# PM_Controller_v1p04.net
KiCad netlist of a schematic drawn in EAGLE
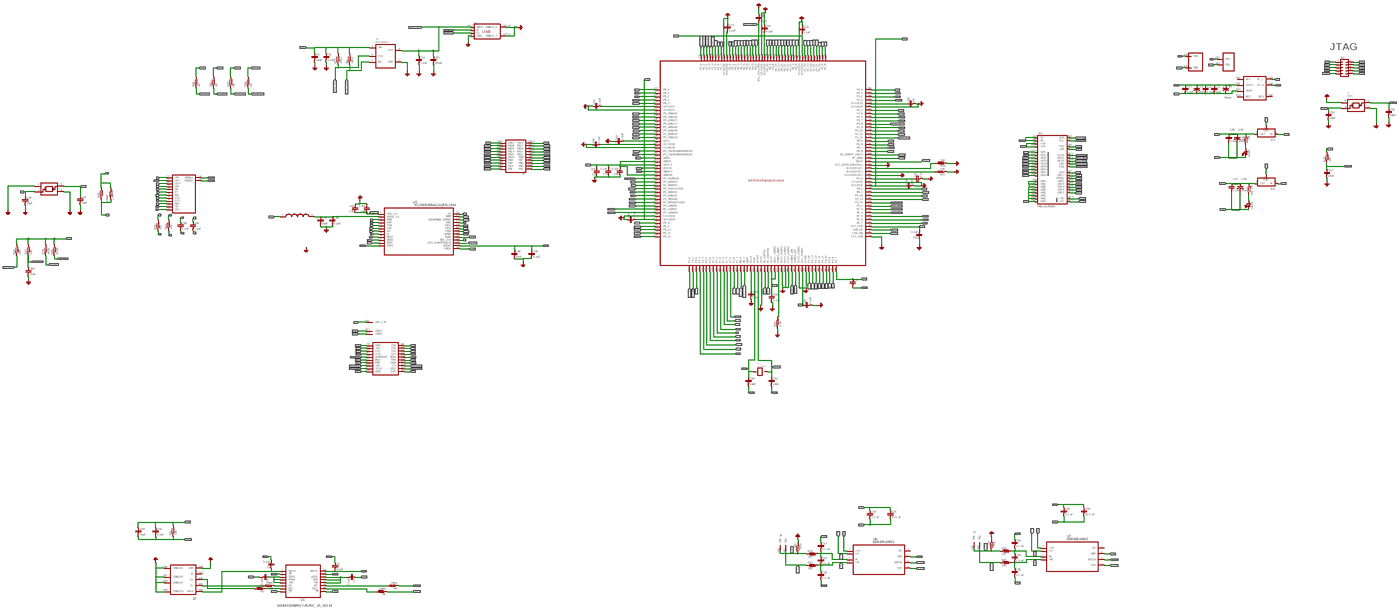
[diagram p0: schematic, sheet 1, overview]
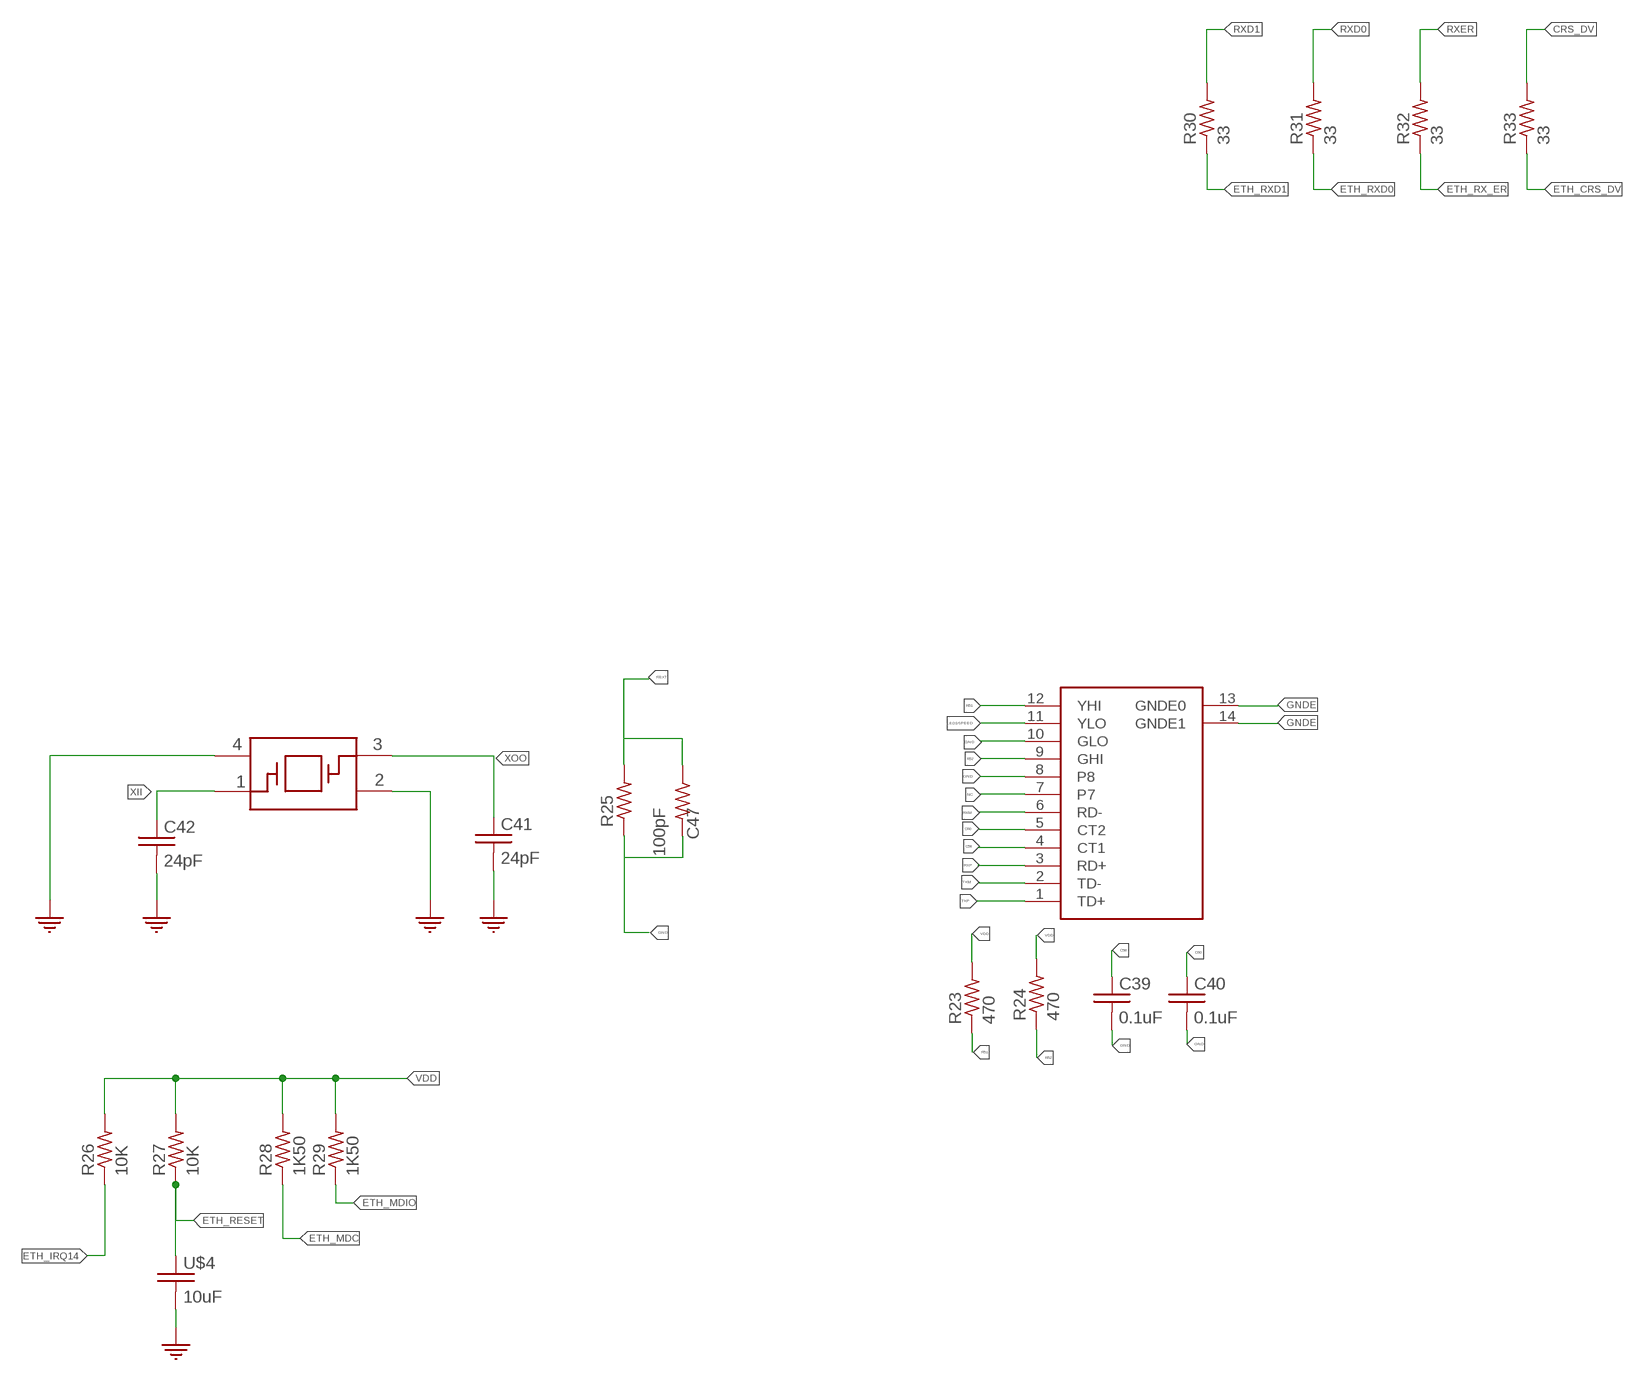
[diagram p1: schematic, sheet 1, part 1 of 7]
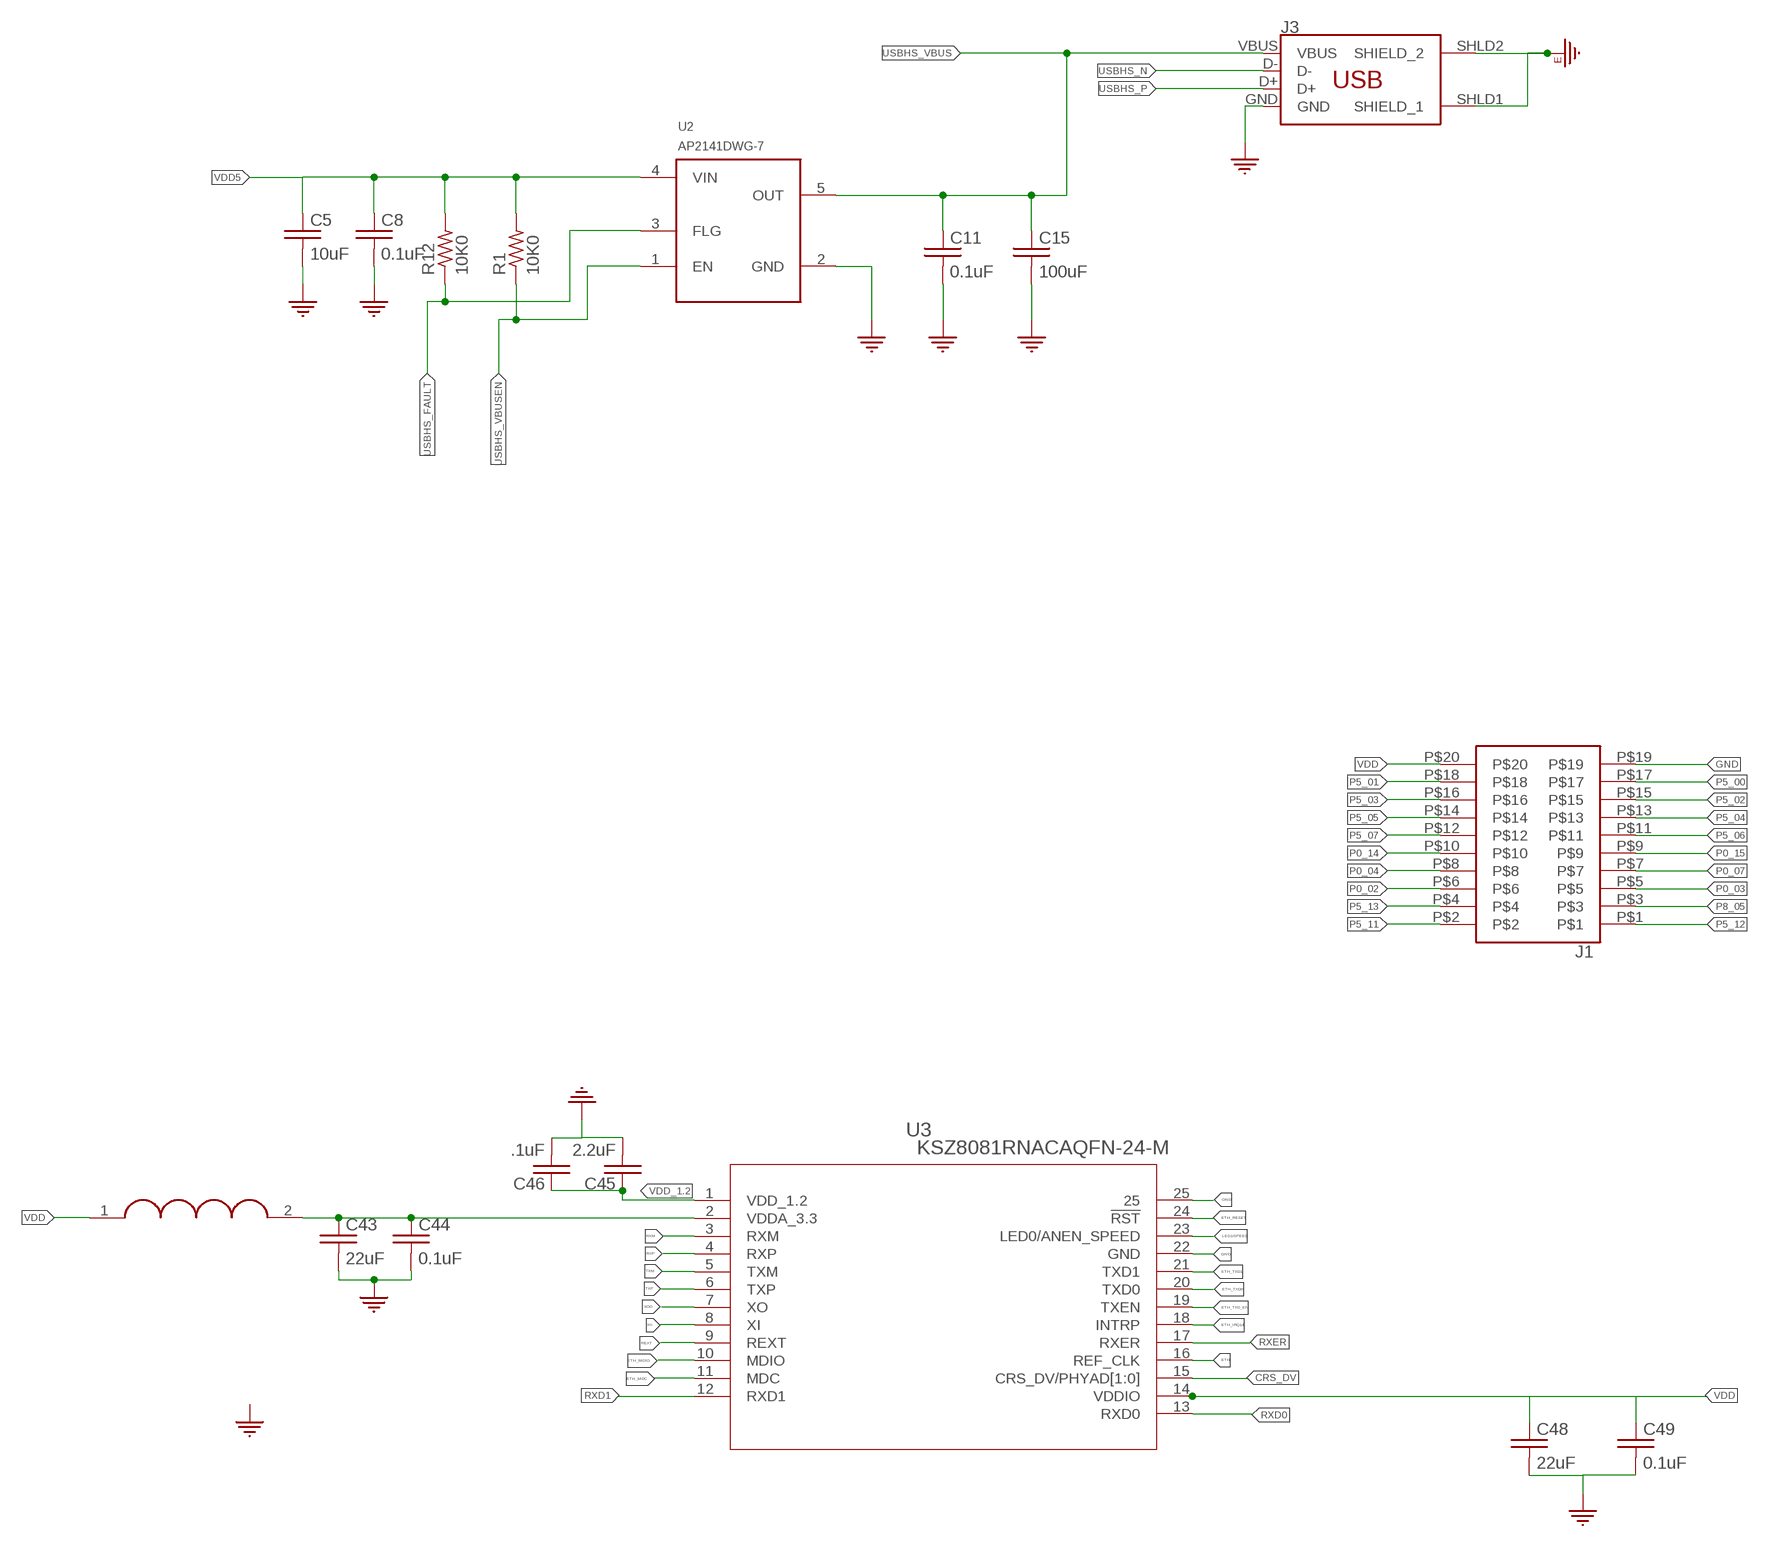
[diagram p2: schematic, sheet 1, part 2 of 7]
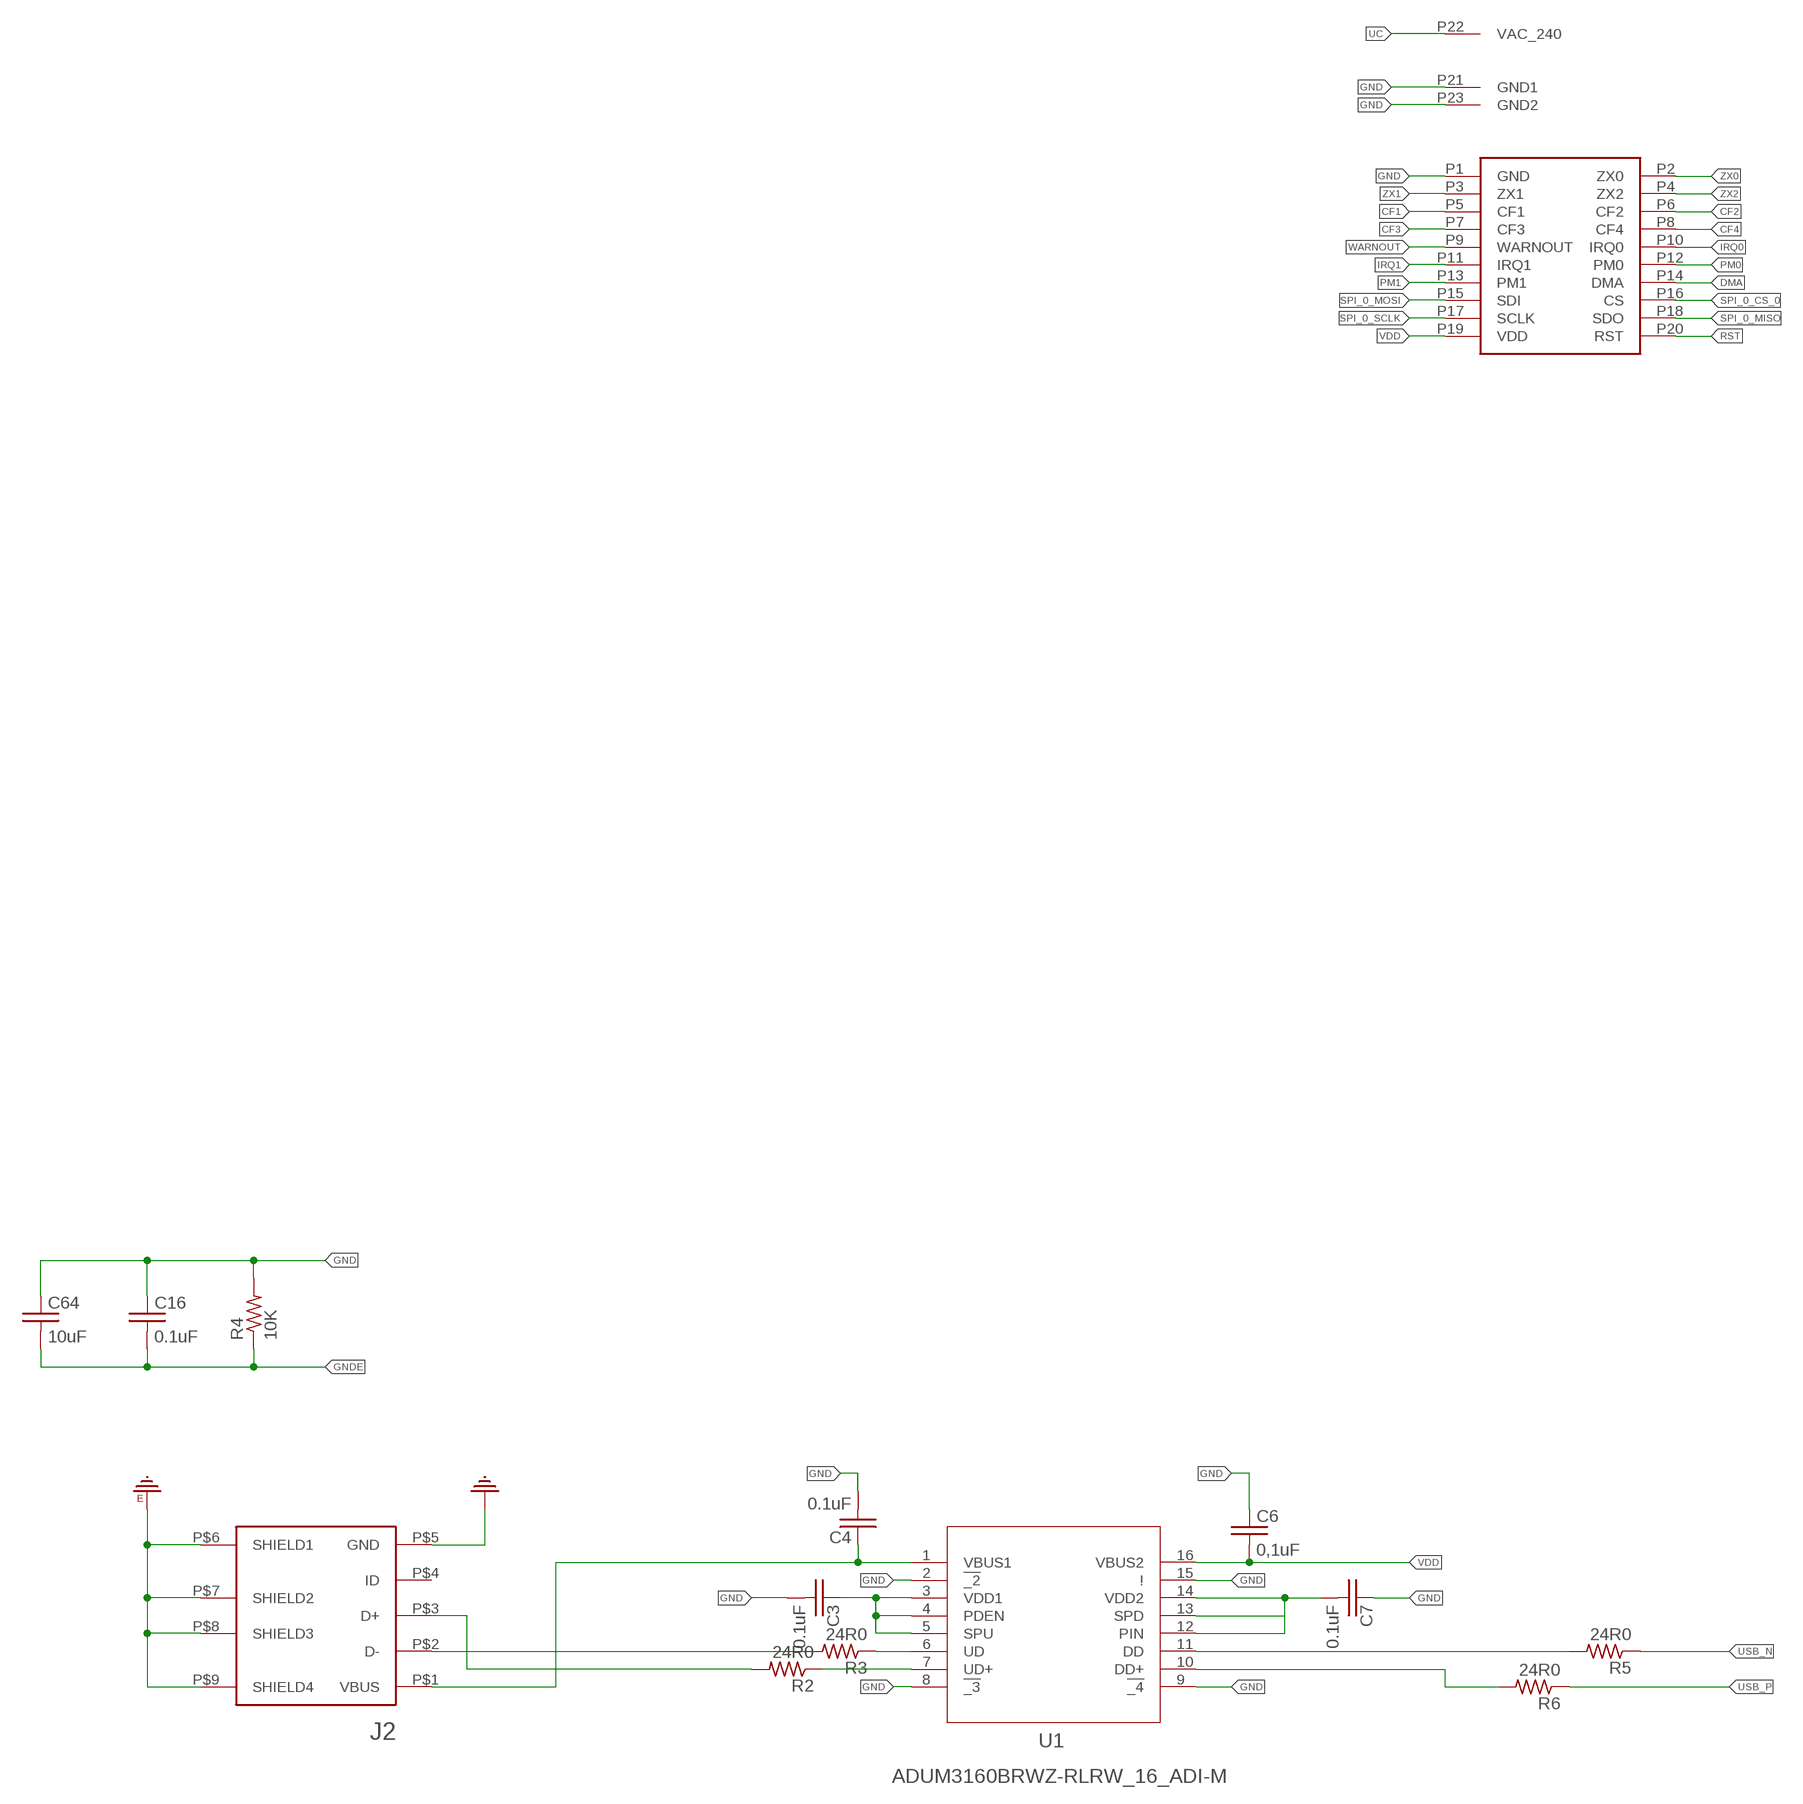
[diagram p3: schematic, sheet 1, part 3 of 7]
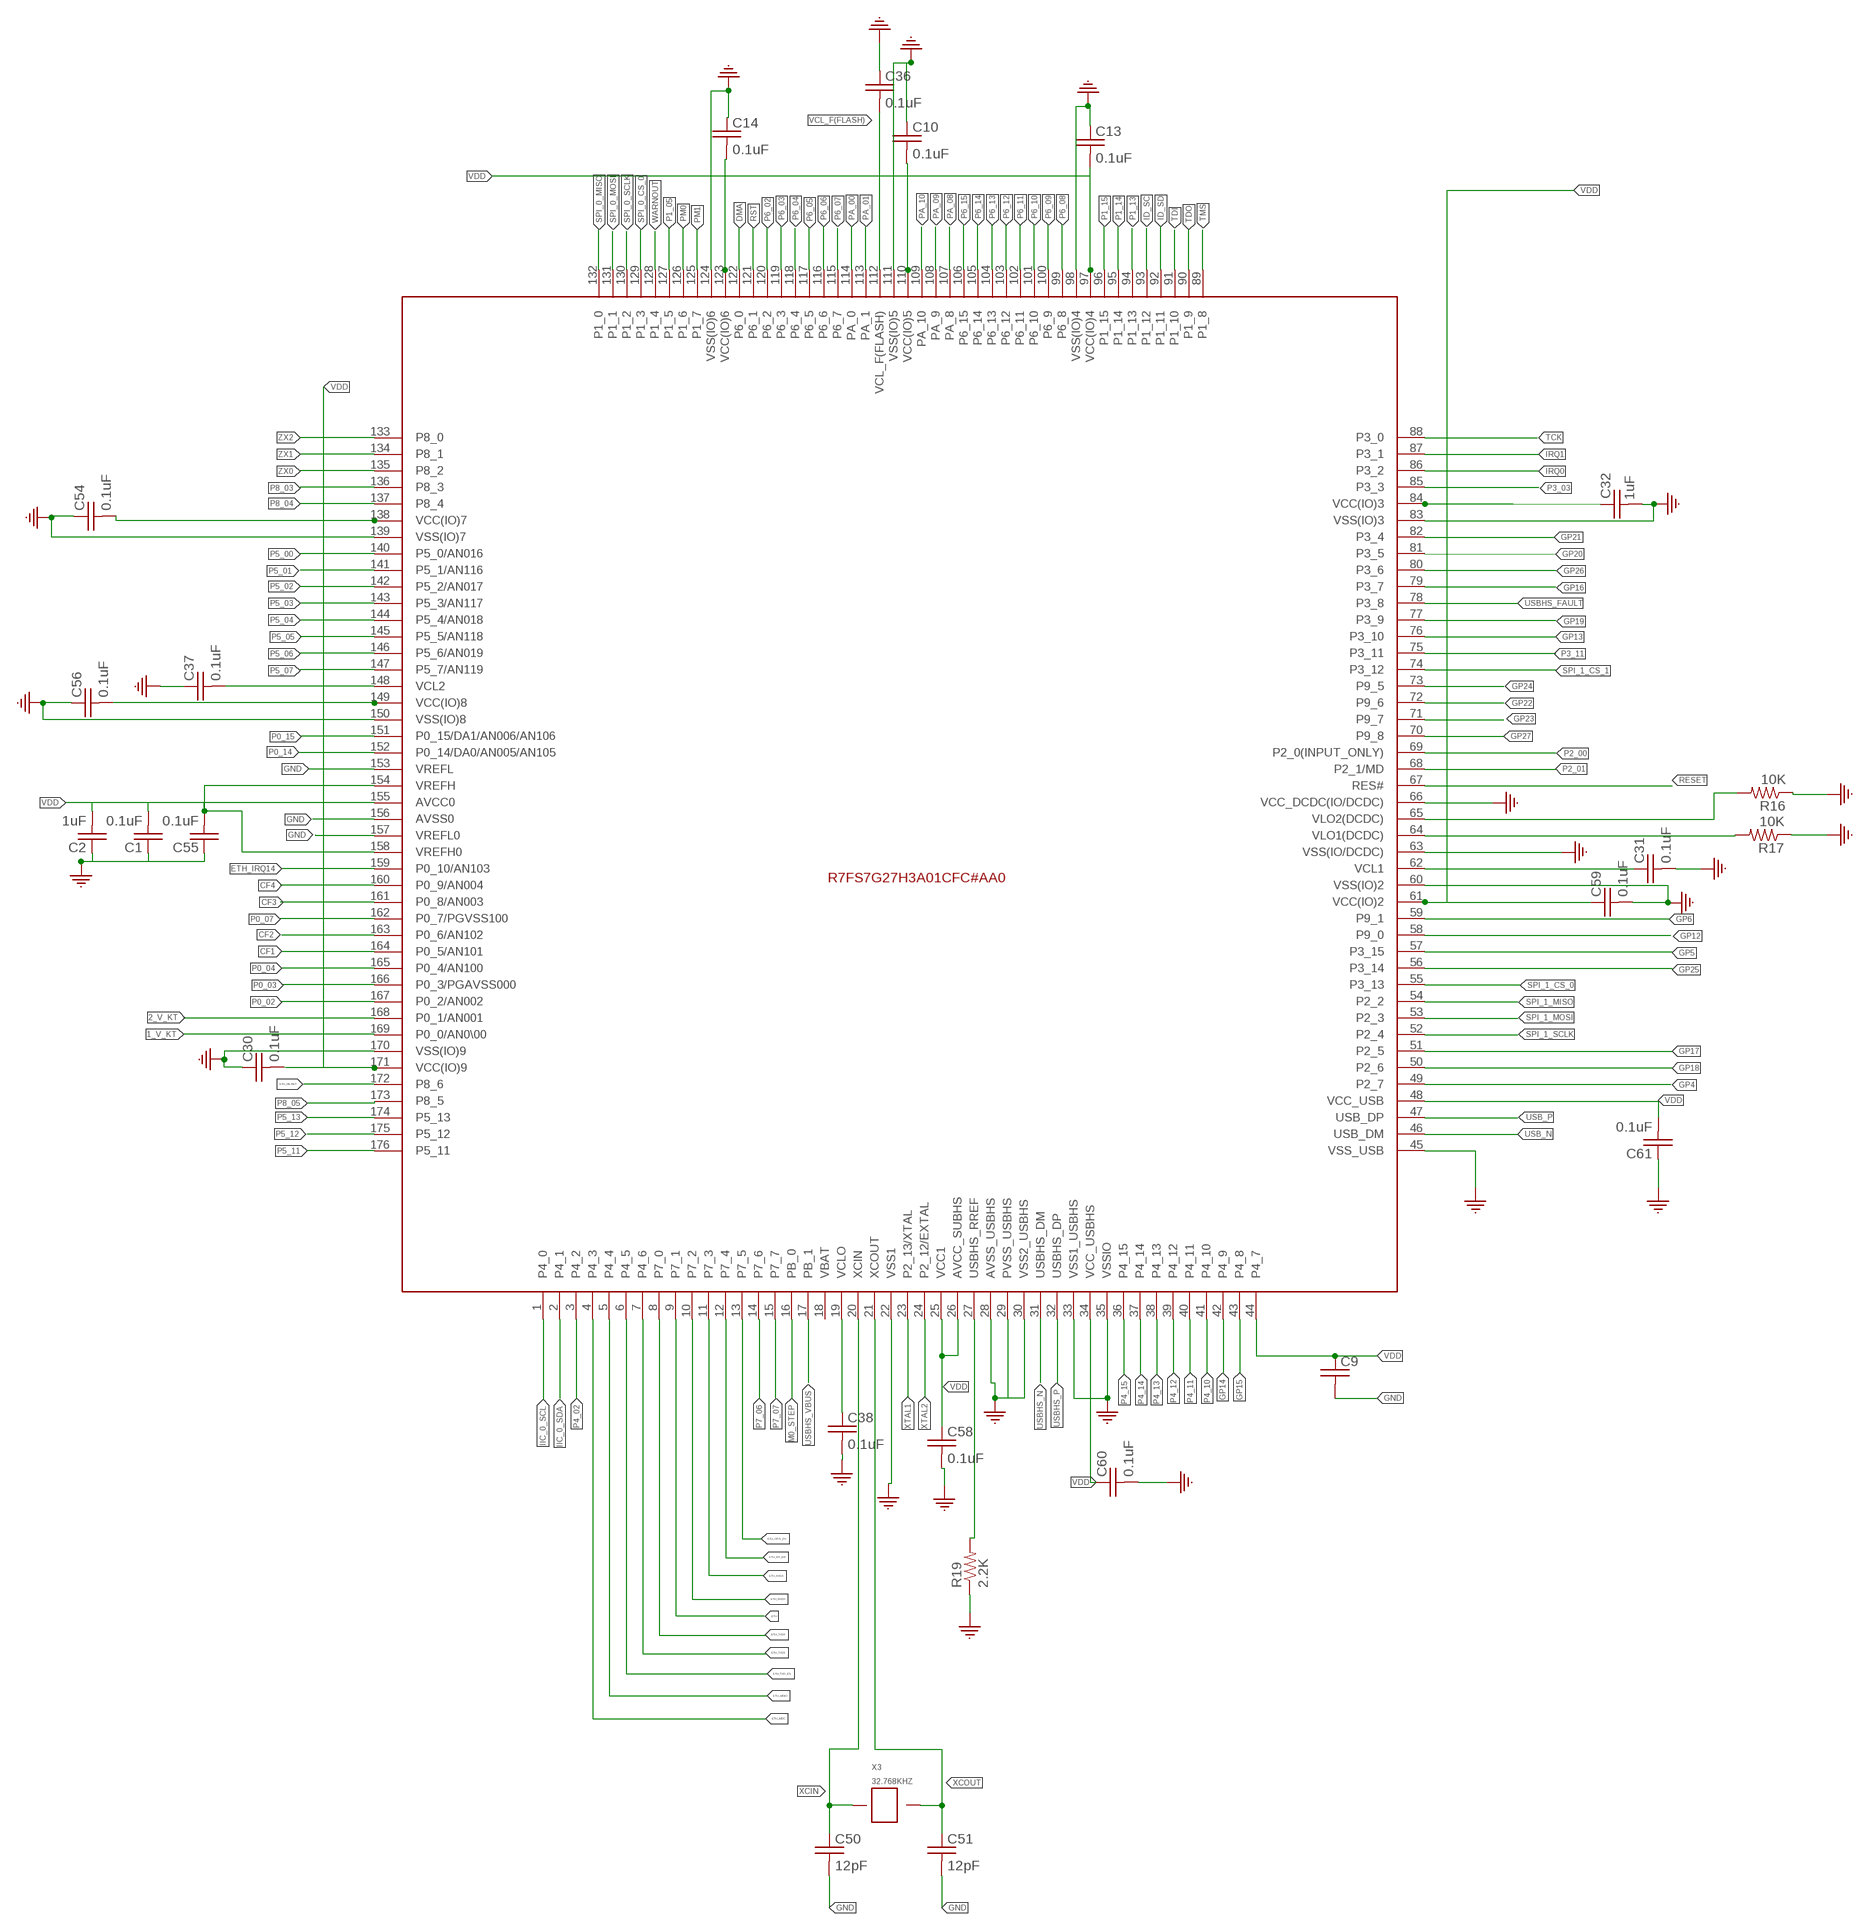
[diagram p4: schematic, sheet 1, part 4 of 7]
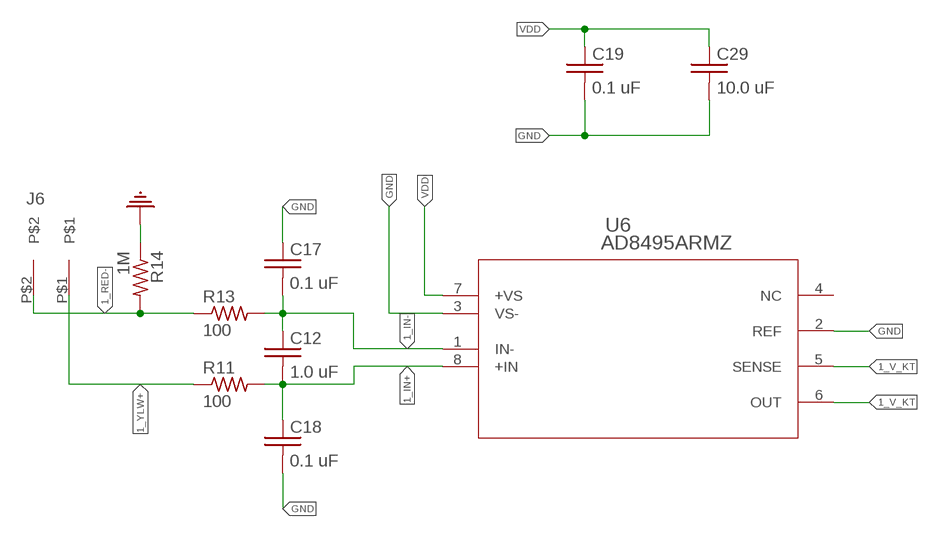
[diagram p5: schematic, sheet 1, part 5 of 7]
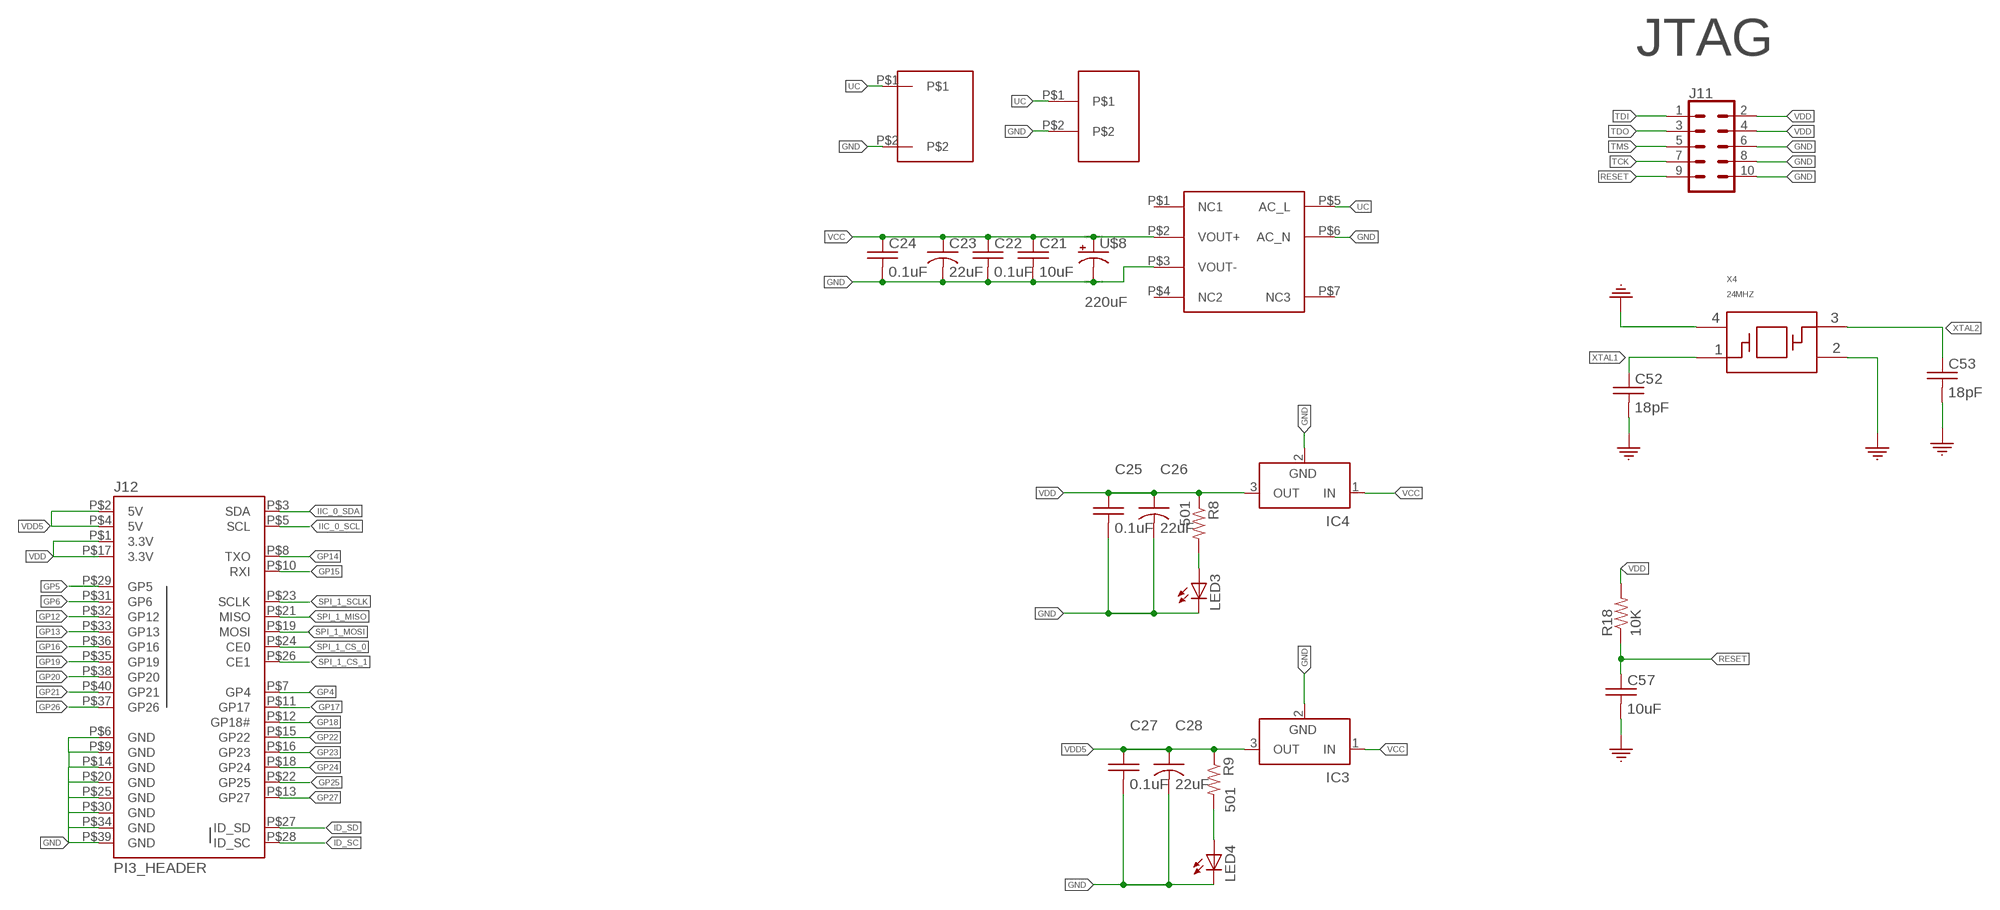
[diagram p6: schematic, sheet 1, part 6 of 7]
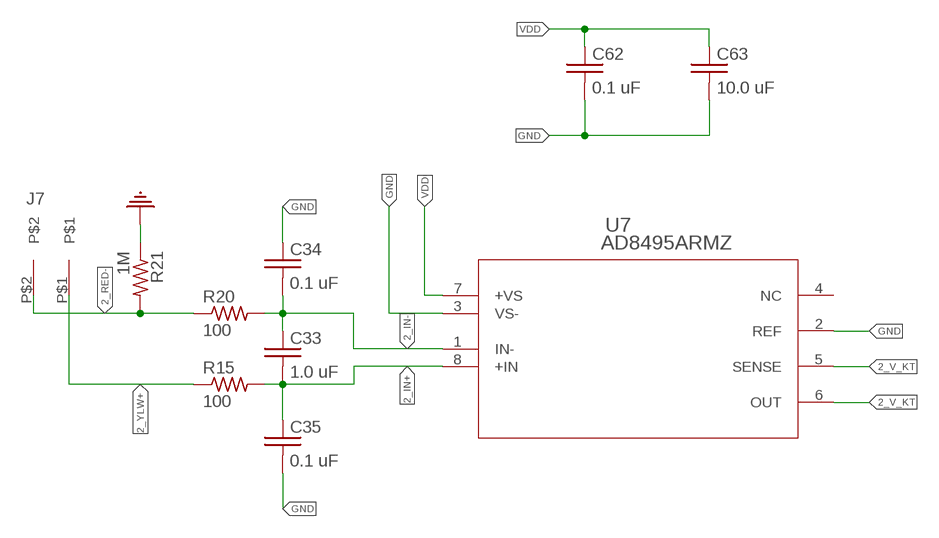
[diagram p7: schematic, sheet 1, part 7 of 7]

(export (version "E")
  (design (tool "Eeschema 10.0.6"))
  (components
    (comp (ref "C1")
      (value "0.1uF")
      (footprint "eagle-import:0402")
      (libsource (lib "eagle-import") (part "C_0402"))
    )
    (comp (ref "C2")
      (value "1uF")
      (footprint "eagle-import:0402")
      (libsource (lib "eagle-import") (part "C_0402"))
    )
    (comp (ref "C3")
      (value "0.1uF")
      (footprint "eagle-import:0402")
      (libsource (lib "eagle-import") (part "C_0402"))
    )
    (comp (ref "C4")
      (value "0.1uF")
      (footprint "eagle-import:0402")
      (libsource (lib "eagle-import") (part "C_0402"))
    )
    (comp (ref "C5")
      (value "10uF")
      (footprint "eagle-import:0402")
      (libsource (lib "eagle-import") (part "C_0402"))
    )
    (comp (ref "C6")
      (value "0,1uF")
      (footprint "eagle-import:0402")
      (libsource (lib "eagle-import") (part "C_0402"))
    )
    (comp (ref "C7")
      (value "0.1uF")
      (footprint "eagle-import:0402")
      (libsource (lib "eagle-import") (part "C_0402"))
    )
    (comp (ref "C8")
      (value "0.1uF")
      (footprint "eagle-import:0402")
      (libsource (lib "eagle-import") (part "C_0402"))
    )
    (comp (ref "C9")
      (value "C_0402")
      (footprint "eagle-import:0402")
      (libsource (lib "eagle-import") (part "C_0402"))
    )
    (comp (ref "C10")
      (value "0.1uF")
      (footprint "eagle-import:0402")
      (libsource (lib "eagle-import") (part "C_0402"))
    )
    (comp (ref "C11")
      (value "0.1uF")
      (footprint "eagle-import:0402")
      (libsource (lib "eagle-import") (part "C_0402"))
    )
    (comp (ref "C12")
      (value "1.0 uF")
      (footprint "eagle-import:0402")
      (libsource (lib "eagle-import") (part "C_0402"))
    )
    (comp (ref "C13")
      (value "0.1uF")
      (footprint "eagle-import:0402")
      (libsource (lib "eagle-import") (part "C_0402"))
    )
    (comp (ref "C14")
      (value "0.1uF")
      (footprint "eagle-import:0402")
      (libsource (lib "eagle-import") (part "C_0402"))
    )
    (comp (ref "C15")
      (value "100uF")
      (footprint "eagle-import:C1210")
      (libsource (lib "eagle-import") (part "C_1210"))
    )
    (comp (ref "C16")
      (value "0.1uF")
      (footprint "eagle-import:0402")
      (libsource (lib "eagle-import") (part "C_0402"))
    )
    (comp (ref "C17")
      (value "0.1 uF")
      (footprint "eagle-import:0402")
      (libsource (lib "eagle-import") (part "C_0402"))
    )
    (comp (ref "C18")
      (value "0.1 uF")
      (footprint "eagle-import:0402")
      (libsource (lib "eagle-import") (part "C_0402"))
    )
    (comp (ref "C19")
      (value "0.1 uF")
      (footprint "eagle-import:0402")
      (libsource (lib "eagle-import") (part "C_0402"))
    )
    (comp (ref "C20")
      (value "CAP_THIN_FILM_TDK_32922CAP")
      (footprint "eagle-import:CAP_THIN_FILM_32922")
      (libsource (lib "eagle-import") (part "CAP_THIN_FILM_TDK_32922CAP"))
    )
    (comp (ref "C21")
      (value "10uF")
      (footprint "eagle-import:0402")
      (libsource (lib "eagle-import") (part "C_0402"))
    )
    (comp (ref "C22")
      (value "0.1uF")
      (footprint "eagle-import:0402")
      (libsource (lib "eagle-import") (part "C_0402"))
    )
    (comp (ref "C23")
      (value "22uF")
      (footprint "eagle-import:C1206")
      (libsource (lib "eagle-import") (part "C-USC1206"))
    )
    (comp (ref "C24")
      (value "0.1uF")
      (footprint "eagle-import:0402")
      (libsource (lib "eagle-import") (part "C_0402"))
    )
    (comp (ref "C25")
      (value "0.1uF")
      (footprint "eagle-import:0402")
      (libsource (lib "eagle-import") (part "C_0402"))
    )
    (comp (ref "C26")
      (value "22uF")
      (footprint "eagle-import:C1206")
      (libsource (lib "eagle-import") (part "C-USC1206"))
    )
    (comp (ref "C27")
      (value "0.1uF")
      (footprint "eagle-import:0402")
      (libsource (lib "eagle-import") (part "C_0402"))
    )
    (comp (ref "C28")
      (value "22uF")
      (footprint "eagle-import:C1206")
      (libsource (lib "eagle-import") (part "C-USC1206"))
    )
    (comp (ref "C29")
      (value "10.0 uF")
      (footprint "eagle-import:0402")
      (libsource (lib "eagle-import") (part "C_0402"))
    )
    (comp (ref "C30")
      (value "0.1uF")
      (footprint "eagle-import:0402")
      (libsource (lib "eagle-import") (part "C_0402"))
    )
    (comp (ref "C31")
      (value "0.1uF")
      (footprint "eagle-import:0402")
      (libsource (lib "eagle-import") (part "C_0402"))
    )
    (comp (ref "C32")
      (value "1uF")
      (footprint "eagle-import:0402")
      (libsource (lib "eagle-import") (part "C_0402"))
    )
    (comp (ref "C33")
      (value "1.0 uF")
      (footprint "eagle-import:0402")
      (libsource (lib "eagle-import") (part "C_0402"))
    )
    (comp (ref "C34")
      (value "0.1 uF")
      (footprint "eagle-import:0402")
      (libsource (lib "eagle-import") (part "C_0402"))
    )
    (comp (ref "C35")
      (value "0.1 uF")
      (footprint "eagle-import:0402")
      (libsource (lib "eagle-import") (part "C_0402"))
    )
    (comp (ref "C36")
      (value "0.1uF")
      (footprint "eagle-import:0402")
      (libsource (lib "eagle-import") (part "C_0402"))
    )
    (comp (ref "C37")
      (value "0.1uF")
      (footprint "eagle-import:0402")
      (libsource (lib "eagle-import") (part "C_0402"))
    )
    (comp (ref "C38")
      (value "0.1uF")
      (footprint "eagle-import:0402")
      (libsource (lib "eagle-import") (part "C_0402"))
    )
    (comp (ref "C39")
      (value "0.1uF")
      (footprint "eagle-import:0402")
      (libsource (lib "eagle-import") (part "C_0402"))
    )
    (comp (ref "C40")
      (value "0.1uF")
      (footprint "eagle-import:0402")
      (libsource (lib "eagle-import") (part "C_0402"))
    )
    (comp (ref "C41")
      (value "24pF")
      (footprint "eagle-import:0402")
      (libsource (lib "eagle-import") (part "C_0402"))
    )
    (comp (ref "C42")
      (value "24pF")
      (footprint "eagle-import:0402")
      (libsource (lib "eagle-import") (part "C_0402"))
    )
    (comp (ref "C43")
      (value "22uF")
      (footprint "eagle-import:0603")
      (libsource (lib "eagle-import") (part "C_0603"))
    )
    (comp (ref "C44")
      (value "0.1uF")
      (footprint "eagle-import:0402")
      (libsource (lib "eagle-import") (part "C_0402"))
    )
    (comp (ref "C45")
      (value "2.2uF")
      (footprint "eagle-import:0402")
      (libsource (lib "eagle-import") (part "C_0402"))
    )
    (comp (ref "C46")
      (value ".1uF")
      (footprint "eagle-import:0402")
      (libsource (lib "eagle-import") (part "C_0402"))
    )
    (comp (ref "C47")
      (value "100pF")
      (footprint "eagle-import:0402")
      (libsource (lib "eagle-import") (part "R_0402"))
    )
    (comp (ref "C48")
      (value "22uF")
      (footprint "eagle-import:0603")
      (libsource (lib "eagle-import") (part "C_0603"))
    )
    (comp (ref "C49")
      (value "0.1uF")
      (footprint "eagle-import:0402")
      (libsource (lib "eagle-import") (part "C_0402"))
    )
    (comp (ref "C50")
      (value "12pF")
      (footprint "eagle-import:0402")
      (libsource (lib "eagle-import") (part "C_0402"))
    )
    (comp (ref "C51")
      (value "12pF")
      (footprint "eagle-import:0402")
      (libsource (lib "eagle-import") (part "C_0402"))
    )
    (comp (ref "C52")
      (value "18pF")
      (footprint "eagle-import:0402")
      (libsource (lib "eagle-import") (part "C_0402"))
    )
    (comp (ref "C53")
      (value "18pF")
      (footprint "eagle-import:0402")
      (libsource (lib "eagle-import") (part "C_0402"))
    )
    (comp (ref "C54")
      (value "0.1uF")
      (footprint "eagle-import:0402")
      (libsource (lib "eagle-import") (part "C_0402"))
    )
    (comp (ref "C55")
      (value "0.1uF")
      (footprint "eagle-import:0402")
      (libsource (lib "eagle-import") (part "C_0402"))
    )
    (comp (ref "C56")
      (value "0.1uF")
      (footprint "eagle-import:0402")
      (libsource (lib "eagle-import") (part "C_0402"))
    )
    (comp (ref "C57")
      (value "10uF")
      (footprint "eagle-import:0402")
      (libsource (lib "eagle-import") (part "C_0402"))
    )
    (comp (ref "C58")
      (value "0.1uF")
      (footprint "eagle-import:0402")
      (libsource (lib "eagle-import") (part "C_0402"))
    )
    (comp (ref "C59")
      (value "0.1uF")
      (footprint "eagle-import:0402")
      (libsource (lib "eagle-import") (part "C_0402"))
    )
    (comp (ref "C60")
      (value "0.1uF")
      (footprint "eagle-import:0402")
      (libsource (lib "eagle-import") (part "C_0402"))
    )
    (comp (ref "C61")
      (value "0.1uF")
      (footprint "eagle-import:0402")
      (libsource (lib "eagle-import") (part "C_0402"))
    )
    (comp (ref "C62")
      (value "0.1 uF")
      (footprint "eagle-import:0402")
      (libsource (lib "eagle-import") (part "C_0402"))
    )
    (comp (ref "C63")
      (value "10.0 uF")
      (footprint "eagle-import:0402")
      (libsource (lib "eagle-import") (part "C_0402"))
    )
    (comp (ref "C64")
      (value "10uF")
      (footprint "eagle-import:0402")
      (libsource (lib "eagle-import") (part "C_0402"))
    )
    (comp (ref "FB2/2")
      (value "FB_0805_120_OHM")
      (footprint "eagle-import:0805")
      (libsource (lib "eagle-import") (part "FB_0805_120_OHM"))
    )
    (comp (ref "IC3")
      (value "LT1129CST5")
      (footprint "eagle-import:SOT223")
      (fields (field (name "MPN") "LT1129CST-5#PBF"))
      (libsource (lib "eagle-import") (part "LT1129CST5"))
    )
    (comp (ref "IC4")
      (value "LT1129CST3")
      (footprint "eagle-import:SOT223")
      (fields (field (name "MPN") "LT1129CST-5#PBF"))
      (libsource (lib "eagle-import") (part "LT1129CST3"))
    )
    (comp (ref "J1")
      (value "2_X_10_HEADER_GENERIC")
      (footprint "eagle-import:2_X_10_.1_INCH")
      (libsource (lib "eagle-import") (part "2_X_10_HEADER_GENERIC"))
    )
    (comp (ref "J2")
      (value "USB_MICRO-B")
      (footprint "eagle-import:USB_MICRO-B")
      (libsource (lib "eagle-import") (part "USB_MICRO-B"))
    )
    (comp (ref "J3")
      (value "USB_A")
      (footprint "eagle-import:USB_A_SMT")
      (libsource (lib "eagle-import") (part "USB_A"))
    )
    (comp (ref "J4")
      (value "RJ45_WITH_ELEC")
      (footprint "eagle-import:RJ45_TH_ELEC")
      (libsource (lib "eagle-import") (part "RJ45_WITH_ELEC"))
    )
    (comp (ref "J6")
      (value "3.81MM_1_X_2_RT_ANGLE_PLUG_HEADER")
      (footprint "eagle-import:2_3.81MM_PITCH")
      (libsource (lib "eagle-import") (part "3.81MM_1_X_2_RT_ANGLE_PLUG_HEADER"))
    )
    (comp (ref "J7")
      (value "3.81MM_1_X_2_RT_ANGLE_PLUG_HEADER")
      (footprint "eagle-import:2_3.81MM_PITCH")
      (libsource (lib "eagle-import") (part "3.81MM_1_X_2_RT_ANGLE_PLUG_HEADER"))
    )
    (comp (ref "J11")
      (value "CONN_05X2PTH")
      (footprint "eagle-import:2X5")
      (libsource (lib "eagle-import") (part "CONN_05X2PTH"))
    )
    (comp (ref "J12")
      (value "PI3_HEADER")
      (footprint "eagle-import:HEADER_2_X_20_.1_INCH")
      (libsource (lib "eagle-import") (part "PI3_HEADER"))
    )
    (comp (ref "LED3")
      (value "LED_0805_GREEN")
      (footprint "eagle-import:LED_0805_GREEN")
      (libsource (lib "eagle-import") (part "LED_0805_GREEN"))
    )
    (comp (ref "LED4")
      (value "LED_0805_GREEN")
      (footprint "eagle-import:LED_0805_GREEN")
      (libsource (lib "eagle-import") (part "LED_0805_GREEN"))
    )
    (comp (ref "R1")
      (value "10K0")
      (footprint "eagle-import:0402")
      (libsource (lib "eagle-import") (part "R_0402"))
    )
    (comp (ref "R2")
      (value "24R0")
      (footprint "eagle-import:0402")
      (libsource (lib "eagle-import") (part "R_0402"))
    )
    (comp (ref "R3")
      (value "24R0")
      (footprint "eagle-import:0402")
      (libsource (lib "eagle-import") (part "R_0402"))
    )
    (comp (ref "R4")
      (value "10K")
      (footprint "eagle-import:0402")
      (libsource (lib "eagle-import") (part "R_0402"))
    )
    (comp (ref "R5")
      (value "24R0")
      (footprint "eagle-import:0402")
      (libsource (lib "eagle-import") (part "R_0402"))
    )
    (comp (ref "R6")
      (value "24R0")
      (footprint "eagle-import:0402")
      (libsource (lib "eagle-import") (part "R_0402"))
    )
    (comp (ref "R8")
      (value "501")
      (footprint "eagle-import:0402")
      (libsource (lib "eagle-import") (part "R_0402"))
    )
    (comp (ref "R9")
      (value "501")
      (footprint "eagle-import:0402")
      (libsource (lib "eagle-import") (part "R_0402"))
    )
    (comp (ref "R11")
      (value "100")
      (footprint "eagle-import:0402")
      (libsource (lib "eagle-import") (part "R_0402"))
    )
    (comp (ref "R12")
      (value "10K0")
      (footprint "eagle-import:0402")
      (libsource (lib "eagle-import") (part "R_0402"))
    )
    (comp (ref "R13")
      (value "100")
      (footprint "eagle-import:0402")
      (libsource (lib "eagle-import") (part "R_0402"))
    )
    (comp (ref "R14")
      (value "1M")
      (footprint "eagle-import:0402")
      (libsource (lib "eagle-import") (part "R_0402"))
    )
    (comp (ref "R15")
      (value "100")
      (footprint "eagle-import:0402")
      (libsource (lib "eagle-import") (part "R_0402"))
    )
    (comp (ref "R16")
      (value "10K")
      (footprint "eagle-import:0402")
      (libsource (lib "eagle-import") (part "R_0402"))
    )
    (comp (ref "R17")
      (value "10K")
      (footprint "eagle-import:0402")
      (libsource (lib "eagle-import") (part "R_0402"))
    )
    (comp (ref "R18")
      (value "10K")
      (footprint "eagle-import:0402")
      (libsource (lib "eagle-import") (part "R_0402"))
    )
    (comp (ref "R19")
      (value "2.2K")
      (footprint "eagle-import:0402")
      (libsource (lib "eagle-import") (part "R_0402"))
    )
    (comp (ref "R20")
      (value "100")
      (footprint "eagle-import:0402")
      (libsource (lib "eagle-import") (part "R_0402"))
    )
    (comp (ref "R21")
      (value "1M")
      (footprint "eagle-import:0402")
      (libsource (lib "eagle-import") (part "R_0402"))
    )
    (comp (ref "R23")
      (value "470")
      (footprint "eagle-import:0402")
      (libsource (lib "eagle-import") (part "R_0402"))
    )
    (comp (ref "R24")
      (value "470")
      (footprint "eagle-import:0402")
      (libsource (lib "eagle-import") (part "R_0402"))
    )
    (comp (ref "R25")
      (value "6k49")
      (footprint "eagle-import:0402")
      (libsource (lib "eagle-import") (part "R_0402"))
    )
    (comp (ref "R26")
      (value "10K")
      (footprint "eagle-import:0402")
      (libsource (lib "eagle-import") (part "R_0402"))
    )
    (comp (ref "R27")
      (value "10K")
      (footprint "eagle-import:0402")
      (libsource (lib "eagle-import") (part "R_0402"))
    )
    (comp (ref "R28")
      (value "1K50")
      (footprint "eagle-import:0402")
      (libsource (lib "eagle-import") (part "R_0402"))
    )
    (comp (ref "R29")
      (value "1K50")
      (footprint "eagle-import:0402")
      (libsource (lib "eagle-import") (part "R_0402"))
    )
    (comp (ref "R30")
      (value "33")
      (footprint "eagle-import:0402")
      (libsource (lib "eagle-import") (part "R_0402"))
    )
    (comp (ref "R31")
      (value "33")
      (footprint "eagle-import:0402")
      (libsource (lib "eagle-import") (part "R_0402"))
    )
    (comp (ref "R32")
      (value "33")
      (footprint "eagle-import:0402")
      (libsource (lib "eagle-import") (part "R_0402"))
    )
    (comp (ref "R33")
      (value "33")
      (footprint "eagle-import:0402")
      (libsource (lib "eagle-import") (part "R_0402"))
    )
    (comp (ref "U$2")
      (value "METER_BASE")
      (footprint "eagle-import:METER_BASE")
      (libsource (lib "eagle-import") (part "METER_BASE"))
    )
    (comp (ref "U$3")
      (value "XTAL_25_MHZ")
      (footprint "eagle-import:SMD_3225")
      (libsource (lib "eagle-import") (part "XTAL_25_MHZ"))
    )
    (comp (ref "U$4")
      (value "10uF")
      (footprint "eagle-import:0402")
      (libsource (lib "eagle-import") (part "C_0402"))
    )
    (comp (ref "U$7")
      (value "VAR_10MM_VDRUS10")
      (footprint "eagle-import:VAR_10MM_VDRUS10")
      (libsource (lib "eagle-import") (part "VAR_10MM_VDRUS10"))
    )
    (comp (ref "U$8")
      (value "220uF")
      (footprint "eagle-import:C_AL_ELECTROLYTIC_SMD_220UF")
      (libsource (lib "eagle-import") (part "C_AL_ELECTROLYTIC_SMD_220UF"))
    )
    (comp (ref "U1")
      (value "ADUM3160BRWZ-RLRW_16_ADI-M")
      (footprint "eagle-import:RW_16_ADI-M")
      (fields
        (field (name "MANUFACTURER_PART_NUMBER") "ADUM3160BRWZ-RL")
        (field (name "COPYRIGHT") "Copyright (C) 2018 Accelerated Designs. All rights reserved")
      )
      (libsource (lib "eagle-import") (part "ADUM3160BRWZ-RLRW_16_ADI-M"))
    )
    (comp (ref "U2")
      (value "AP2141DWG-5")
      (footprint "eagle-import:SOT-23-5")
      (libsource (lib "eagle-import") (part "AP2141DWG-5"))
    )
    (comp (ref "U3")
      (value "KSZ8081RNACAQFN-24-M")
      (footprint "eagle-import:QFN-24-M")
      (fields (field (name "MANUFACTURER_PART_NUMBER") "KSZ8081RNACA"))
      (libsource (lib "eagle-import") (part "KSZ8081RNACAQFN-24-M"))
    )
    (comp (ref "U4")
      (value "S7G2_X_176")
      (footprint "eagle-import:LQFP176_24X24")
      (libsource (lib "eagle-import") (part "S7G2_X_176"))
    )
    (comp (ref "U5")
      (value "TMLM_04109")
      (footprint "eagle-import:TMLM04")
      (libsource (lib "eagle-import") (part "TMLM_04109"))
    )
    (comp (ref "U6")
      (value "AD8495ARMZ")
      (footprint "eagle-import:RM_8_ADI")
      (libsource (lib "eagle-import") (part "AD8495ARMZ"))
    )
    (comp (ref "U7")
      (value "AD8495ARMZ")
      (footprint "eagle-import:RM_8_ADI")
      (libsource (lib "eagle-import") (part "AD8495ARMZ"))
    )
    (comp (ref "X3")
      (value "32.768KHZ")
      (footprint "eagle-import:SMD_X_2_PADS")
      (libsource (lib "eagle-import") (part "XTAL_32.768KHZ"))
    )
    (comp (ref "X4")
      (value "24MHZ")
      (footprint "eagle-import:SMD_3225")
      (libsource (lib "eagle-import") (part "XTAL_24_MHZ"))
    )
  )
  (nets
    (net (code "1") (name "1_IN+") (class "Default")
      (node (ref "C12") (pin "P$2") (pinfunction "2_P$2") (pintype "passive"))
      (node (ref "C18") (pin "P$1") (pinfunction "1_P$1") (pintype "passive"))
      (node (ref "R11") (pin "P$2") (pinfunction "2_P$2") (pintype "passive"))
      (node (ref "U6") (pin "8") (pinfunction "+IN_8") (pintype "input"))
    )
    (net (code "2") (name "1_IN-") (class "Default")
      (node (ref "C12") (pin "P$1") (pinfunction "1_P$1") (pintype "passive"))
      (node (ref "C17") (pin "P$2") (pinfunction "2_P$2") (pintype "passive"))
      (node (ref "R13") (pin "P$2") (pinfunction "2_P$2") (pintype "passive"))
      (node (ref "U6") (pin "1") (pinfunction "IN-_1") (pintype "input"))
    )
    (net (code "3") (name "1_RED-") (class "Default")
      (node (ref "J6") (pin "P$2") (pinfunction "P$2_P$2") (pintype "bidirectional"))
      (node (ref "R13") (pin "P$1") (pinfunction "1_P$1") (pintype "passive"))
      (node (ref "R14") (pin "P$2") (pinfunction "2_P$2") (pintype "passive"))
    )
    (net (code "4") (name "1_V_KT") (class "Default")
      (node (ref "U4") (pin "169") (pinfunction "P0_0/AN0\\00_169") (pintype "bidirectional"))
      (node (ref "U6") (pin "5") (pinfunction "SENSE_5") (pintype "passive"))
      (node (ref "U6") (pin "6") (pinfunction "OUT_6") (pintype "output"))
    )
    (net (code "5") (name "1_YLW+") (class "Default")
      (node (ref "J6") (pin "P$1") (pinfunction "P$1_P$1") (pintype "bidirectional"))
      (node (ref "R11") (pin "P$1") (pinfunction "1_P$1") (pintype "passive"))
    )
    (net (code "6") (name "2_IN+") (class "Default")
      (node (ref "C33") (pin "P$2") (pinfunction "2_P$2") (pintype "passive"))
      (node (ref "C35") (pin "P$1") (pinfunction "1_P$1") (pintype "passive"))
      (node (ref "R15") (pin "P$2") (pinfunction "2_P$2") (pintype "passive"))
      (node (ref "U7") (pin "8") (pinfunction "+IN_8") (pintype "input"))
    )
    (net (code "7") (name "2_IN-") (class "Default")
      (node (ref "C33") (pin "P$1") (pinfunction "1_P$1") (pintype "passive"))
      (node (ref "C34") (pin "P$2") (pinfunction "2_P$2") (pintype "passive"))
      (node (ref "R20") (pin "P$2") (pinfunction "2_P$2") (pintype "passive"))
      (node (ref "U7") (pin "1") (pinfunction "IN-_1") (pintype "input"))
    )
    (net (code "8") (name "2_RED-") (class "Default")
      (node (ref "J7") (pin "P$2") (pinfunction "P$2_P$2") (pintype "bidirectional"))
      (node (ref "R20") (pin "P$1") (pinfunction "1_P$1") (pintype "passive"))
      (node (ref "R21") (pin "P$2") (pinfunction "2_P$2") (pintype "passive"))
    )
    (net (code "9") (name "2_V_KT") (class "Default")
      (node (ref "U4") (pin "168") (pinfunction "P0_1/AN001_168") (pintype "bidirectional"))
      (node (ref "U7") (pin "5") (pinfunction "SENSE_5") (pintype "passive"))
      (node (ref "U7") (pin "6") (pinfunction "OUT_6") (pintype "output"))
    )
    (net (code "10") (name "2_YLW+") (class "Default")
      (node (ref "J7") (pin "P$1") (pinfunction "P$1_P$1") (pintype "bidirectional"))
      (node (ref "R15") (pin "P$1") (pinfunction "1_P$1") (pintype "passive"))
    )
    (net (code "11") (name "C58") (class "Default")
      (node (ref "C39") (pin "P$1") (pinfunction "1_P$1") (pintype "passive"))
      (node (ref "J4") (pin "4") (pinfunction "CT1_4") (pintype "bidirectional"))
    )
    (net (code "12") (name "C60") (class "Default")
      (node (ref "C40") (pin "P$1") (pinfunction "1_P$1") (pintype "passive"))
      (node (ref "J4") (pin "5") (pinfunction "CT2_5") (pintype "bidirectional"))
    )
    (net (code "13") (name "CF1") (class "Default")
      (node (ref "U$2") (pin "P5") (pinfunction "CF1_P5") (pintype "bidirectional"))
      (node (ref "U4") (pin "164") (pinfunction "P0_5/AN101_164") (pintype "bidirectional"))
    )
    (net (code "14") (name "CF2") (class "Default")
      (node (ref "U$2") (pin "P6") (pinfunction "CF2_P6") (pintype "bidirectional"))
      (node (ref "U4") (pin "163") (pinfunction "P0_6/AN102_163") (pintype "bidirectional"))
    )
    (net (code "15") (name "CF3") (class "Default")
      (node (ref "U$2") (pin "P7") (pinfunction "CF3_P7") (pintype "bidirectional"))
      (node (ref "U4") (pin "161") (pinfunction "P0_8/AN003_161") (pintype "bidirectional"))
    )
    (net (code "16") (name "CF4") (class "Default")
      (node (ref "U$2") (pin "P8") (pinfunction "CF4_P8") (pintype "bidirectional"))
      (node (ref "U4") (pin "160") (pinfunction "P0_9/AN004_160") (pintype "bidirectional"))
    )
    (net (code "17") (name "CRS_DV") (class "Default")
      (node (ref "R33") (pin "P$2") (pinfunction "2_P$2") (pintype "passive"))
      (node (ref "U3") (pin "15") (pinfunction "CRS_DV/PHYAD[1:0]_15") (pintype "bidirectional"))
    )
    (net (code "18") (name "DMA") (class "Default")
      (node (ref "U$2") (pin "P14") (pinfunction "DMA_P14") (pintype "bidirectional"))
      (node (ref "U4") (pin "122") (pinfunction "P6_0_122") (pintype "bidirectional"))
    )
    (net (code "19") (name "ETH") (class "Default")
      (node (ref "U3") (pin "16") (pinfunction "REF_CLK_16") (pintype "bidirectional"))
      (node (ref "U4") (pin "9") (pinfunction "P7_1_9") (pintype "bidirectional"))
    )
    (net (code "20") (name "ETH_CRS_DV") (class "Default")
      (node (ref "R33") (pin "P$1") (pinfunction "1_P$1") (pintype "passive"))
      (node (ref "U4") (pin "13") (pinfunction "P7_5_13") (pintype "bidirectional"))
    )
    (net (code "21") (name "ETH_IRQ14") (class "Default")
      (node (ref "R26") (pin "P$1") (pinfunction "1_P$1") (pintype "passive"))
      (node (ref "U3") (pin "18") (pinfunction "INTRP_18") (pintype "bidirectional"))
      (node (ref "U4") (pin "159") (pinfunction "P0_10/AN103_159") (pintype "bidirectional"))
    )
    (net (code "22") (name "ETH_MDC") (class "Default")
      (node (ref "R28") (pin "P$1") (pinfunction "1_P$1") (pintype "passive"))
      (node (ref "U3") (pin "11") (pinfunction "MDC_11") (pintype "input"))
      (node (ref "U4") (pin "4") (pinfunction "P4_3_4") (pintype "bidirectional"))
    )
    (net (code "23") (name "ETH_MDIO") (class "Default")
      (node (ref "R29") (pin "P$1") (pinfunction "1_P$1") (pintype "passive"))
      (node (ref "U3") (pin "10") (pinfunction "MDIO_10") (pintype "bidirectional"))
      (node (ref "U4") (pin "5") (pinfunction "P4_4_5") (pintype "bidirectional"))
    )
    (net (code "24") (name "ETH_RESET") (class "Default")
      (node (ref "R27") (pin "P$1") (pinfunction "1_P$1") (pintype "passive"))
      (node (ref "U$4") (pin "P$1") (pinfunction "1_P$1") (pintype "passive"))
      (node (ref "U3") (pin "24") (pinfunction "~{RST}_24") (pintype "input"))
      (node (ref "U4") (pin "172") (pinfunction "P8_6_172") (pintype "bidirectional"))
    )
    (net (code "25") (name "ETH_RXD0") (class "Default")
      (node (ref "R31") (pin "P$1") (pinfunction "1_P$1") (pintype "passive"))
      (node (ref "U4") (pin "10") (pinfunction "P7_2_10") (pintype "bidirectional"))
    )
    (net (code "26") (name "ETH_RXD1") (class "Default")
      (node (ref "R30") (pin "P$1") (pinfunction "1_P$1") (pintype "passive"))
      (node (ref "U4") (pin "11") (pinfunction "P7_3_11") (pintype "bidirectional"))
    )
    (net (code "27") (name "ETH_RX_ER") (class "Default")
      (node (ref "R32") (pin "P$1") (pinfunction "1_P$1") (pintype "passive"))
      (node (ref "U4") (pin "12") (pinfunction "P7_4_12") (pintype "bidirectional"))
    )
    (net (code "28") (name "ETH_TXD0") (class "Default")
      (node (ref "U3") (pin "20") (pinfunction "TXD0_20") (pintype "input"))
      (node (ref "U4") (pin "8") (pinfunction "P7_0_8") (pintype "bidirectional"))
    )
    (net (code "29") (name "ETH_TXD1") (class "Default")
      (node (ref "U3") (pin "21") (pinfunction "TXD1_21") (pintype "bidirectional"))
      (node (ref "U4") (pin "7") (pinfunction "P4_6_7") (pintype "bidirectional"))
    )
    (net (code "30") (name "ETH_TXD_EN") (class "Default")
      (node (ref "U3") (pin "19") (pinfunction "TXEN_19") (pintype "input"))
      (node (ref "U4") (pin "6") (pinfunction "P4_5_6") (pintype "bidirectional"))
    )
    (net (code "31") (name "GND") (class "Default")
      (node (ref "C1") (pin "P$1") (pinfunction "1_P$1") (pintype "passive"))
      (node (ref "C10") (pin "P$1") (pinfunction "1_P$1") (pintype "passive"))
      (node (ref "C11") (pin "P$2") (pinfunction "2_P$2") (pintype "passive"))
      (node (ref "C13") (pin "P$1") (pinfunction "1_P$1") (pintype "passive"))
      (node (ref "C14") (pin "P$1") (pinfunction "1_P$1") (pintype "passive"))
      (node (ref "C15") (pin "2") (pinfunction "2_2") (pintype "passive"))
      (node (ref "C16") (pin "P$1") (pinfunction "1_P$1") (pintype "passive"))
      (node (ref "C17") (pin "P$1") (pinfunction "1_P$1") (pintype "passive"))
      (node (ref "C18") (pin "P$2") (pinfunction "2_P$2") (pintype "passive"))
      (node (ref "C19") (pin "P$2") (pinfunction "2_P$2") (pintype "passive"))
      (node (ref "C2") (pin "P$1") (pinfunction "1_P$1") (pintype "passive"))
      (node (ref "C20") (pin "P$2") (pinfunction "P$2_P$2") (pintype "bidirectional"))
      (node (ref "C21") (pin "P$2") (pinfunction "2_P$2") (pintype "passive"))
      (node (ref "C22") (pin "P$2") (pinfunction "2_P$2") (pintype "passive"))
      (node (ref "C23") (pin "2") (pinfunction "2_2") (pintype "passive"))
      (node (ref "C24") (pin "P$2") (pinfunction "2_P$2") (pintype "passive"))
      (node (ref "C25") (pin "P$2") (pinfunction "2_P$2") (pintype "passive"))
      (node (ref "C26") (pin "2") (pinfunction "2_2") (pintype "passive"))
      (node (ref "C27") (pin "P$2") (pinfunction "2_P$2") (pintype "passive"))
      (node (ref "C28") (pin "2") (pinfunction "2_2") (pintype "passive"))
      (node (ref "C29") (pin "P$2") (pinfunction "2_P$2") (pintype "passive"))
      (node (ref "C3") (pin "P$2") (pinfunction "2_P$2") (pintype "passive"))
      (node (ref "C30") (pin "P$1") (pinfunction "1_P$1") (pintype "passive"))
      (node (ref "C31") (pin "P$2") (pinfunction "2_P$2") (pintype "passive"))
      (node (ref "C32") (pin "P$2") (pinfunction "2_P$2") (pintype "passive"))
      (node (ref "C34") (pin "P$1") (pinfunction "1_P$1") (pintype "passive"))
      (node (ref "C35") (pin "P$2") (pinfunction "2_P$2") (pintype "passive"))
      (node (ref "C36") (pin "P$1") (pinfunction "1_P$1") (pintype "passive"))
      (node (ref "C37") (pin "P$1") (pinfunction "1_P$1") (pintype "passive"))
      (node (ref "C38") (pin "P$2") (pinfunction "2_P$2") (pintype "passive"))
      (node (ref "C39") (pin "P$2") (pinfunction "2_P$2") (pintype "passive"))
      (node (ref "C4") (pin "P$2") (pinfunction "2_P$2") (pintype "passive"))
      (node (ref "C40") (pin "P$2") (pinfunction "2_P$2") (pintype "passive"))
      (node (ref "C41") (pin "P$2") (pinfunction "2_P$2") (pintype "passive"))
      (node (ref "C42") (pin "P$2") (pinfunction "2_P$2") (pintype "passive"))
      (node (ref "C43") (pin "2") (pinfunction "2_2") (pintype "passive"))
      (node (ref "C44") (pin "P$2") (pinfunction "2_P$2") (pintype "passive"))
      (node (ref "C45") (pin "P$2") (pinfunction "2_P$2") (pintype "passive"))
      (node (ref "C46") (pin "P$2") (pinfunction "2_P$2") (pintype "passive"))
      (node (ref "C47") (pin "P$2") (pinfunction "2_P$2") (pintype "passive"))
      (node (ref "C48") (pin "2") (pinfunction "2_2") (pintype "passive"))
      (node (ref "C49") (pin "P$2") (pinfunction "2_P$2") (pintype "passive"))
      (node (ref "C5") (pin "P$2") (pinfunction "2_P$2") (pintype "passive"))
      (node (ref "C50") (pin "P$2") (pinfunction "2_P$2") (pintype "passive"))
      (node (ref "C51") (pin "P$2") (pinfunction "2_P$2") (pintype "passive"))
      (node (ref "C52") (pin "P$2") (pinfunction "2_P$2") (pintype "passive"))
      (node (ref "C53") (pin "P$2") (pinfunction "2_P$2") (pintype "passive"))
      (node (ref "C54") (pin "P$1") (pinfunction "1_P$1") (pintype "passive"))
      (node (ref "C55") (pin "P$1") (pinfunction "1_P$1") (pintype "passive"))
      (node (ref "C56") (pin "P$1") (pinfunction "1_P$1") (pintype "passive"))
      (node (ref "C57") (pin "P$2") (pinfunction "2_P$2") (pintype "passive"))
      (node (ref "C58") (pin "P$2") (pinfunction "2_P$2") (pintype "passive"))
      (node (ref "C59") (pin "P$2") (pinfunction "2_P$2") (pintype "passive"))
      (node (ref "C6") (pin "P$1") (pinfunction "1_P$1") (pintype "passive"))
      (node (ref "C60") (pin "P$2") (pinfunction "2_P$2") (pintype "passive"))
      (node (ref "C61") (pin "P$1") (pinfunction "1_P$1") (pintype "passive"))
      (node (ref "C62") (pin "P$2") (pinfunction "2_P$2") (pintype "passive"))
      (node (ref "C63") (pin "P$2") (pinfunction "2_P$2") (pintype "passive"))
      (node (ref "C64") (pin "P$1") (pinfunction "1_P$1") (pintype "passive"))
      (node (ref "C7") (pin "P$1") (pinfunction "1_P$1") (pintype "passive"))
      (node (ref "C8") (pin "P$2") (pinfunction "2_P$2") (pintype "passive"))
      (node (ref "C9") (pin "P$2") (pinfunction "2_P$2") (pintype "passive"))
      (node (ref "IC3") (pin "2") (pinfunction "GND_2") (pintype "power_in"))
      (node (ref "IC4") (pin "2") (pinfunction "GND_2") (pintype "power_in"))
      (node (ref "J1") (pin "P$19") (pinfunction "P$19_P$19") (pintype "bidirectional"))
      (node (ref "J11") (pin "10") (pinfunction "10_10") (pintype "passive"))
      (node (ref "J11") (pin "6") (pinfunction "6_6") (pintype "passive"))
      (node (ref "J11") (pin "8") (pinfunction "8_8") (pintype "passive"))
      (node (ref "J12") (pin "P$14") (pinfunction "GND_P$14") (pintype "power_in"))
      (node (ref "J12") (pin "P$20") (pinfunction "GND_P$20") (pintype "power_in"))
      (node (ref "J12") (pin "P$25") (pinfunction "GND_P$25") (pintype "power_in"))
      (node (ref "J12") (pin "P$30") (pinfunction "GND_P$30") (pintype "power_in"))
      (node (ref "J12") (pin "P$34") (pinfunction "GND_P$34") (pintype "power_in"))
      (node (ref "J12") (pin "P$39") (pinfunction "GND_P$39") (pintype "power_in"))
      (node (ref "J12") (pin "P$6") (pinfunction "GND_P$6") (pintype "power_in"))
      (node (ref "J12") (pin "P$9") (pinfunction "GND_P$9") (pintype "power_in"))
      (node (ref "J2") (pin "P$5") (pinfunction "GND_P$5") (pintype "bidirectional"))
      (node (ref "J3") (pin "GND") (pinfunction "GND_GND") (pintype "power_in"))
      (node (ref "J4") (pin "10") (pinfunction "GLO_10") (pintype "bidirectional"))
      (node (ref "J4") (pin "8") (pinfunction "P8_8") (pintype "bidirectional"))
      (node (ref "LED3") (pin "C") (pinfunction "C_C") (pintype "passive"))
      (node (ref "LED4") (pin "C") (pinfunction "C_C") (pintype "passive"))
      (node (ref "R14") (pin "P$1") (pinfunction "1_P$1") (pintype "passive"))
      (node (ref "R16") (pin "P$1") (pinfunction "1_P$1") (pintype "passive"))
      (node (ref "R17") (pin "P$1") (pinfunction "1_P$1") (pintype "passive"))
      (node (ref "R19") (pin "P$1") (pinfunction "1_P$1") (pintype "passive"))
      (node (ref "R21") (pin "P$1") (pinfunction "1_P$1") (pintype "passive"))
      (node (ref "R25") (pin "P$1") (pinfunction "1_P$1") (pintype "passive"))
      (node (ref "R4") (pin "P$2") (pinfunction "2_P$2") (pintype "passive"))
      (node (ref "U$2") (pin "P1") (pinfunction "GND_P1") (pintype "bidirectional"))
      (node (ref "U$2") (pin "P21") (pinfunction "GND1_P21") (pintype "bidirectional"))
      (node (ref "U$2") (pin "P23") (pinfunction "GND2_P23") (pintype "bidirectional"))
      (node (ref "U$3") (pin "2") (pinfunction "2_2") (pintype "bidirectional"))
      (node (ref "U$3") (pin "4") (pinfunction "4_4") (pintype "bidirectional"))
      (node (ref "U$4") (pin "P$2") (pinfunction "2_P$2") (pintype "passive"))
      (node (ref "U$7") (pin "P$2") (pinfunction "P$2_P$2") (pintype "bidirectional"))
      (node (ref "U$8") (pin "N-") (pinfunction "-_N-") (pintype "passive"))
      (node (ref "U1") (pin "15") (pinfunction "~_15") (pintype "passive"))
      (node (ref "U1") (pin "2") (pinfunction "~{_2}_2") (pintype "passive"))
      (node (ref "U1") (pin "8") (pinfunction "~{_3}_8") (pintype "passive"))
      (node (ref "U1") (pin "9") (pinfunction "~{_4}_9") (pintype "passive"))
      (node (ref "U2") (pin "2") (pinfunction "GND_2") (pintype "input"))
      (node (ref "U3") (pin "22") (pinfunction "GND_22") (pintype "power_in"))
      (node (ref "U3") (pin "25") (pinfunction "25_25") (pintype "passive"))
      (node (ref "U4") (pin "111") (pinfunction "VSS(IO)5_111") (pintype "bidirectional"))
      (node (ref "U4") (pin "124") (pinfunction "VSS(IO)6_124") (pintype "bidirectional"))
      (node (ref "U4") (pin "139") (pinfunction "VSS(IO)7_139") (pintype "bidirectional"))
      (node (ref "U4") (pin "150") (pinfunction "VSS(IO)8_150") (pintype "bidirectional"))
      (node (ref "U4") (pin "153") (pinfunction "VREFL_153") (pintype "bidirectional"))
      (node (ref "U4") (pin "156") (pinfunction "AVSS0_156") (pintype "bidirectional"))
      (node (ref "U4") (pin "157") (pinfunction "VREFL0_157") (pintype "bidirectional"))
      (node (ref "U4") (pin "170") (pinfunction "VSS(IO)9_170") (pintype "bidirectional"))
      (node (ref "U4") (pin "22") (pinfunction "VSS1_22") (pintype "bidirectional"))
      (node (ref "U4") (pin "28") (pinfunction "AVSS_USBHS_28") (pintype "bidirectional"))
      (node (ref "U4") (pin "29") (pinfunction "PVSS_USBHS_29") (pintype "bidirectional"))
      (node (ref "U4") (pin "30") (pinfunction "VSS2_USBHS_30") (pintype "bidirectional"))
      (node (ref "U4") (pin "33") (pinfunction "VSS1_USBHS_33") (pintype "bidirectional"))
      (node (ref "U4") (pin "35") (pinfunction "VSSIO_35") (pintype "bidirectional"))
      (node (ref "U4") (pin "45") (pinfunction "VSS_USB_45") (pintype "bidirectional"))
      (node (ref "U4") (pin "60") (pinfunction "VSS(IO)2_60") (pintype "bidirectional"))
      (node (ref "U4") (pin "63") (pinfunction "VSS(IO/DCDC)_63") (pintype "bidirectional"))
      (node (ref "U4") (pin "66") (pinfunction "VCC_DCDC(IO/DCDC)_66") (pintype "bidirectional"))
      (node (ref "U4") (pin "83") (pinfunction "VSS(IO)3_83") (pintype "bidirectional"))
      (node (ref "U4") (pin "98") (pinfunction "VSS(IO)4_98") (pintype "bidirectional"))
      (node (ref "U5") (pin "P$3") (pinfunction "VOUT-_P$3") (pintype "bidirectional"))
      (node (ref "U5") (pin "P$6") (pinfunction "AC_N_P$6") (pintype "bidirectional"))
      (node (ref "U6") (pin "2") (pinfunction "REF_2") (pintype "passive"))
      (node (ref "U6") (pin "3") (pinfunction "VS-_3") (pintype "power_in"))
      (node (ref "U7") (pin "2") (pinfunction "REF_2") (pintype "passive"))
      (node (ref "U7") (pin "3") (pinfunction "VS-_3") (pintype "power_in"))
      (node (ref "X4") (pin "2") (pinfunction "2_2") (pintype "bidirectional"))
      (node (ref "X4") (pin "4") (pinfunction "4_4") (pintype "bidirectional"))
    )
    (net (code "32") (name "GNDE") (class "Default")
      (node (ref "C16") (pin "P$2") (pinfunction "2_P$2") (pintype "passive"))
      (node (ref "C64") (pin "P$2") (pinfunction "2_P$2") (pintype "passive"))
      (node (ref "J2") (pin "P$6") (pinfunction "SHIELD1_P$6") (pintype "bidirectional"))
      (node (ref "J2") (pin "P$7") (pinfunction "SHIELD2_P$7") (pintype "bidirectional"))
      (node (ref "J2") (pin "P$8") (pinfunction "SHIELD3_P$8") (pintype "bidirectional"))
      (node (ref "J2") (pin "P$9") (pinfunction "SHIELD4_P$9") (pintype "bidirectional"))
      (node (ref "J3") (pin "SHLD1") (pinfunction "SHIELD_1_SHLD1") (pintype "bidirectional"))
      (node (ref "J3") (pin "SHLD2") (pinfunction "SHIELD_2_SHLD2") (pintype "bidirectional"))
      (node (ref "J4") (pin "13") (pinfunction "GNDE0_13") (pintype "bidirectional"))
      (node (ref "J4") (pin "14") (pinfunction "GNDE1_14") (pintype "bidirectional"))
      (node (ref "R4") (pin "P$1") (pinfunction "1_P$1") (pintype "passive"))
    )
    (net (code "33") (name "GP4") (class "Default")
      (node (ref "J12") (pin "P$7") (pinfunction "GP4_P$7") (pintype "bidirectional"))
      (node (ref "U4") (pin "49") (pinfunction "P2_7_49") (pintype "bidirectional"))
    )
    (net (code "34") (name "GP5") (class "Default")
      (node (ref "J12") (pin "P$29") (pinfunction "GP5_P$29") (pintype "bidirectional"))
      (node (ref "U4") (pin "57") (pinfunction "P3_15_57") (pintype "bidirectional"))
    )
    (net (code "35") (name "GP6") (class "Default")
      (node (ref "J12") (pin "P$31") (pinfunction "GP6_P$31") (pintype "bidirectional"))
      (node (ref "U4") (pin "59") (pinfunction "P9_1_59") (pintype "bidirectional"))
    )
    (net (code "36") (name "GP12") (class "Default")
      (node (ref "J12") (pin "P$32") (pinfunction "GP12_P$32") (pintype "bidirectional"))
      (node (ref "U4") (pin "58") (pinfunction "P9_0_58") (pintype "bidirectional"))
    )
    (net (code "37") (name "GP13") (class "Default")
      (node (ref "J12") (pin "P$33") (pinfunction "GP13_P$33") (pintype "bidirectional"))
      (node (ref "U4") (pin "76") (pinfunction "P3_10_76") (pintype "bidirectional"))
    )
    (net (code "38") (name "GP14") (class "Default")
      (node (ref "J12") (pin "P$8") (pinfunction "TXO_P$8") (pintype "output"))
      (node (ref "U4") (pin "42") (pinfunction "P4_9_42") (pintype "bidirectional"))
    )
    (net (code "39") (name "GP15") (class "Default")
      (node (ref "J12") (pin "P$10") (pinfunction "RXI_P$10") (pintype "input"))
      (node (ref "U4") (pin "43") (pinfunction "P4_8_43") (pintype "bidirectional"))
    )
    (net (code "40") (name "GP16") (class "Default")
      (node (ref "J12") (pin "P$36") (pinfunction "GP16_P$36") (pintype "bidirectional"))
      (node (ref "U4") (pin "79") (pinfunction "P3_7_79") (pintype "bidirectional"))
    )
    (net (code "41") (name "GP17") (class "Default")
      (node (ref "J12") (pin "P$11") (pinfunction "GP17_P$11") (pintype "bidirectional"))
      (node (ref "U4") (pin "51") (pinfunction "P2_5_51") (pintype "bidirectional"))
    )
    (net (code "42") (name "GP18") (class "Default")
      (node (ref "J12") (pin "P$12") (pinfunction "GP18#_P$12") (pintype "bidirectional"))
      (node (ref "U4") (pin "50") (pinfunction "P2_6_50") (pintype "bidirectional"))
    )
    (net (code "43") (name "GP19") (class "Default")
      (node (ref "J12") (pin "P$35") (pinfunction "GP19_P$35") (pintype "bidirectional"))
      (node (ref "U4") (pin "77") (pinfunction "P3_9_77") (pintype "bidirectional"))
    )
    (net (code "44") (name "GP20") (class "Default")
      (node (ref "J12") (pin "P$38") (pinfunction "GP20_P$38") (pintype "bidirectional"))
      (node (ref "U4") (pin "81") (pinfunction "P3_5_81") (pintype "bidirectional"))
    )
    (net (code "45") (name "GP21") (class "Default")
      (node (ref "J12") (pin "P$40") (pinfunction "GP21_P$40") (pintype "bidirectional"))
      (node (ref "U4") (pin "82") (pinfunction "P3_4_82") (pintype "bidirectional"))
    )
    (net (code "46") (name "GP22") (class "Default")
      (node (ref "J12") (pin "P$15") (pinfunction "GP22_P$15") (pintype "bidirectional"))
      (node (ref "U4") (pin "72") (pinfunction "P9_6_72") (pintype "bidirectional"))
    )
    (net (code "47") (name "GP23") (class "Default")
      (node (ref "J12") (pin "P$16") (pinfunction "GP23_P$16") (pintype "bidirectional"))
      (node (ref "U4") (pin "71") (pinfunction "P9_7_71") (pintype "bidirectional"))
    )
    (net (code "48") (name "GP24") (class "Default")
      (node (ref "J12") (pin "P$18") (pinfunction "GP24_P$18") (pintype "bidirectional"))
      (node (ref "U4") (pin "73") (pinfunction "P9_5_73") (pintype "bidirectional"))
    )
    (net (code "49") (name "GP25") (class "Default")
      (node (ref "J12") (pin "P$22") (pinfunction "GP25_P$22") (pintype "bidirectional"))
      (node (ref "U4") (pin "56") (pinfunction "P3_14_56") (pintype "bidirectional"))
    )
    (net (code "50") (name "GP26") (class "Default")
      (node (ref "J12") (pin "P$37") (pinfunction "GP26_P$37") (pintype "bidirectional"))
      (node (ref "U4") (pin "80") (pinfunction "P3_6_80") (pintype "bidirectional"))
    )
    (net (code "51") (name "GP27") (class "Default")
      (node (ref "J12") (pin "P$13") (pinfunction "GP27_P$13") (pintype "bidirectional"))
      (node (ref "U4") (pin "70") (pinfunction "P9_8_70") (pintype "bidirectional"))
    )
    (net (code "52") (name "ID_SC") (class "Default")
      (node (ref "J12") (pin "P$28") (pinfunction "ID_SC_P$28") (pintype "bidirectional"))
      (node (ref "U4") (pin "93") (pinfunction "P1_12_93") (pintype "bidirectional"))
    )
    (net (code "53") (name "ID_SD") (class "Default")
      (node (ref "J12") (pin "P$27") (pinfunction "ID_SD_P$27") (pintype "bidirectional"))
      (node (ref "U4") (pin "92") (pinfunction "P1_11_92") (pintype "bidirectional"))
    )
    (net (code "54") (name "IIC_0_SCL") (class "Default")
      (node (ref "J12") (pin "P$5") (pinfunction "SCL_P$5") (pintype "bidirectional"))
      (node (ref "U4") (pin "1") (pinfunction "P4_0_1") (pintype "bidirectional"))
    )
    (net (code "55") (name "IIC_0_SDA") (class "Default")
      (node (ref "J12") (pin "P$3") (pinfunction "SDA_P$3") (pintype "bidirectional"))
      (node (ref "U4") (pin "2") (pinfunction "P4_1_2") (pintype "bidirectional"))
    )
    (net (code "56") (name "IRQ0") (class "Default")
      (node (ref "U$2") (pin "P10") (pinfunction "IRQ0_P10") (pintype "bidirectional"))
      (node (ref "U4") (pin "86") (pinfunction "P3_2_86") (pintype "bidirectional"))
    )
    (net (code "57") (name "IRQ1") (class "Default")
      (node (ref "U$2") (pin "P11") (pinfunction "IRQ1_P11") (pintype "bidirectional"))
      (node (ref "U4") (pin "87") (pinfunction "P3_1_87") (pintype "bidirectional"))
    )
    (net (code "58") (name "LED1{slash}SPEED") (class "Default")
      (node (ref "J4") (pin "11") (pinfunction "YLO_11") (pintype "bidirectional"))
      (node (ref "U3") (pin "23") (pinfunction "LED0/ANEN_SPEED_23") (pintype "bidirectional"))
    )
    (net (code "59") (name "M0_STEP") (class "Default")
      (node (ref "U4") (pin "16") (pinfunction "PB_0_16") (pintype "bidirectional"))
    )
    (net (code "60") (name "NC") (class "Default")
      (node (ref "J4") (pin "7") (pinfunction "P7_7") (pintype "bidirectional"))
    )
    (net (code "61") (name "Net-(C3-1)") (class "Default")
      (node (ref "C3") (pin "P$1") (pinfunction "1_P$1") (pintype "passive"))
      (node (ref "U1") (pin "3") (pinfunction "VDD1_3") (pintype "power_in"))
      (node (ref "U1") (pin "4") (pinfunction "PDEN_4") (pintype "passive"))
      (node (ref "U1") (pin "5") (pinfunction "SPU_5") (pintype "passive"))
    )
    (net (code "62") (name "Net-(C4-1)") (class "Default")
      (node (ref "C4") (pin "P$1") (pinfunction "1_P$1") (pintype "passive"))
      (node (ref "J2") (pin "P$1") (pinfunction "VBUS_P$1") (pintype "bidirectional"))
      (node (ref "U1") (pin "1") (pinfunction "VBUS1_1") (pintype "bidirectional"))
    )
    (net (code "63") (name "Net-(C7-2)") (class "Default")
      (node (ref "C7") (pin "P$2") (pinfunction "2_P$2") (pintype "passive"))
      (node (ref "U1") (pin "12") (pinfunction "PIN_12") (pintype "passive"))
      (node (ref "U1") (pin "13") (pinfunction "SPD_13") (pintype "passive"))
      (node (ref "U1") (pin "14") (pinfunction "VDD2_14") (pintype "power_in"))
    )
    (net (code "64") (name "Net-(C31-1)") (class "Default")
      (node (ref "C31") (pin "P$1") (pinfunction "1_P$1") (pintype "passive"))
      (node (ref "U4") (pin "62") (pinfunction "VCL1_62") (pintype "bidirectional"))
    )
    (net (code "65") (name "Net-(C37-2)") (class "Default")
      (node (ref "C37") (pin "P$2") (pinfunction "2_P$2") (pintype "passive"))
      (node (ref "U4") (pin "148") (pinfunction "VCL2_148") (pintype "bidirectional"))
    )
    (net (code "66") (name "Net-(C38-1)") (class "Default")
      (node (ref "C38") (pin "P$1") (pinfunction "1_P$1") (pintype "passive"))
      (node (ref "U4") (pin "19") (pinfunction "VCLO_19") (pintype "bidirectional"))
    )
    (net (code "67") (name "Net-(C44-1)") (class "Default")
      (node (ref "C43") (pin "1") (pinfunction "1_1") (pintype "passive"))
      (node (ref "C44") (pin "P$1") (pinfunction "1_P$1") (pintype "passive"))
      (node (ref "FB2/2") (pin "2") (pinfunction "P$2_2") (pintype "bidirectional"))
      (node (ref "U3") (pin "2") (pinfunction "VDDA_3.3_2") (pintype "power_in"))
    )
    (net (code "68") (name "Net-(J2-D+)") (class "Default")
      (node (ref "J2") (pin "P$3") (pinfunction "D+_P$3") (pintype "bidirectional"))
      (node (ref "R2") (pin "P$2") (pinfunction "2_P$2") (pintype "passive"))
    )
    (net (code "69") (name "Net-(J2-D-)") (class "Default")
      (node (ref "J2") (pin "P$2") (pinfunction "D-_P$2") (pintype "bidirectional"))
      (node (ref "R3") (pin "P$2") (pinfunction "2_P$2") (pintype "passive"))
    )
    (net (code "70") (name "Net-(R2-1)") (class "Default")
      (node (ref "R2") (pin "P$1") (pinfunction "1_P$1") (pintype "passive"))
      (node (ref "U1") (pin "7") (pinfunction "UD+_7") (pintype "passive"))
    )
    (net (code "71") (name "Net-(R3-1)") (class "Default")
      (node (ref "R3") (pin "P$1") (pinfunction "1_P$1") (pintype "passive"))
      (node (ref "U1") (pin "6") (pinfunction "UD_6") (pintype "passive"))
    )
    (net (code "72") (name "Net-(R5-2)") (class "Default")
      (node (ref "R5") (pin "P$2") (pinfunction "2_P$2") (pintype "passive"))
      (node (ref "U1") (pin "11") (pinfunction "DD_11") (pintype "passive"))
    )
    (net (code "73") (name "Net-(R6-2)") (class "Default")
      (node (ref "R6") (pin "P$2") (pinfunction "2_P$2") (pintype "passive"))
      (node (ref "U1") (pin "10") (pinfunction "DD+_10") (pintype "passive"))
    )
    (net (code "74") (name "Net-(R8-2)") (class "Default")
      (node (ref "LED3") (pin "A") (pinfunction "A_A") (pintype "passive"))
      (node (ref "R8") (pin "P$2") (pinfunction "2_P$2") (pintype "passive"))
    )
    (net (code "75") (name "Net-(R9-2)") (class "Default")
      (node (ref "LED4") (pin "A") (pinfunction "A_A") (pintype "passive"))
      (node (ref "R9") (pin "P$2") (pinfunction "2_P$2") (pintype "passive"))
    )
    (net (code "76") (name "Net-(R16-2)") (class "Default")
      (node (ref "R16") (pin "P$2") (pinfunction "2_P$2") (pintype "passive"))
      (node (ref "U4") (pin "65") (pinfunction "VLO2(DCDC)_65") (pintype "bidirectional"))
    )
    (net (code "77") (name "Net-(R17-2)") (class "Default")
      (node (ref "R17") (pin "P$2") (pinfunction "2_P$2") (pintype "passive"))
      (node (ref "U4") (pin "64") (pinfunction "VLO1(DCDC)_64") (pintype "bidirectional"))
    )
    (net (code "78") (name "Net-(R19-2)") (class "Default")
      (node (ref "R19") (pin "P$2") (pinfunction "2_P$2") (pintype "passive"))
      (node (ref "U4") (pin "27") (pinfunction "USBHS_RREF_27") (pintype "bidirectional"))
    )
    (net (code "79") (name "P0_02") (class "Default")
      (node (ref "J1") (pin "P$6") (pinfunction "P$6_P$6") (pintype "bidirectional"))
      (node (ref "U4") (pin "167") (pinfunction "P0_2/AN002_167") (pintype "bidirectional"))
    )
    (net (code "80") (name "P0_03") (class "Default")
      (node (ref "J1") (pin "P$5") (pinfunction "P$5_P$5") (pintype "bidirectional"))
      (node (ref "U4") (pin "166") (pinfunction "P0_3/PGAVSS000_166") (pintype "bidirectional"))
    )
    (net (code "81") (name "P0_04") (class "Default")
      (node (ref "J1") (pin "P$8") (pinfunction "P$8_P$8") (pintype "bidirectional"))
      (node (ref "U4") (pin "165") (pinfunction "P0_4/AN100_165") (pintype "bidirectional"))
    )
    (net (code "82") (name "P0_07") (class "Default")
      (node (ref "J1") (pin "P$7") (pinfunction "P$7_P$7") (pintype "bidirectional"))
      (node (ref "U4") (pin "162") (pinfunction "P0_7/PGVSS100_162") (pintype "bidirectional"))
    )
    (net (code "83") (name "P0_14") (class "Default")
      (node (ref "J1") (pin "P$10") (pinfunction "P$10_P$10") (pintype "bidirectional"))
      (node (ref "U4") (pin "152") (pinfunction "P0_14/DA0/AN005/AN105_152") (pintype "bidirectional"))
    )
    (net (code "84") (name "P0_15") (class "Default")
      (node (ref "J1") (pin "P$9") (pinfunction "P$9_P$9") (pintype "bidirectional"))
      (node (ref "U4") (pin "151") (pinfunction "P0_15/DA1/AN006/AN106_151") (pintype "bidirectional"))
    )
    (net (code "85") (name "P1_05") (class "Default")
      (node (ref "U4") (pin "127") (pinfunction "P1_5_127") (pintype "bidirectional"))
    )
    (net (code "86") (name "P1_13") (class "Default")
      (node (ref "U4") (pin "94") (pinfunction "P1_13_94") (pintype "bidirectional"))
    )
    (net (code "87") (name "P1_14") (class "Default")
      (node (ref "U4") (pin "95") (pinfunction "P1_14_95") (pintype "bidirectional"))
    )
    (net (code "88") (name "P1_15") (class "Default")
      (node (ref "U4") (pin "96") (pinfunction "P1_15_96") (pintype "bidirectional"))
    )
    (net (code "89") (name "P2_00") (class "Default")
      (node (ref "U4") (pin "69") (pinfunction "P2_0(INPUT_ONLY)_69") (pintype "bidirectional"))
    )
    (net (code "90") (name "P2_01") (class "Default")
      (node (ref "U4") (pin "68") (pinfunction "P2_1/MD_68") (pintype "bidirectional"))
    )
    (net (code "91") (name "P3_03") (class "Default")
      (node (ref "U4") (pin "85") (pinfunction "P3_3_85") (pintype "bidirectional"))
    )
    (net (code "92") (name "P3_11") (class "Default")
      (node (ref "U4") (pin "75") (pinfunction "P3_11_75") (pintype "bidirectional"))
    )
    (net (code "93") (name "P4_02") (class "Default")
      (node (ref "U4") (pin "3") (pinfunction "P4_2_3") (pintype "bidirectional"))
    )
    (net (code "94") (name "P4_10") (class "Default")
      (node (ref "U4") (pin "41") (pinfunction "P4_10_41") (pintype "bidirectional"))
    )
    (net (code "95") (name "P4_11") (class "Default")
      (node (ref "U4") (pin "40") (pinfunction "P4_11_40") (pintype "bidirectional"))
    )
    (net (code "96") (name "P4_12") (class "Default")
      (node (ref "U4") (pin "39") (pinfunction "P4_12_39") (pintype "bidirectional"))
    )
    (net (code "97") (name "P4_13") (class "Default")
      (node (ref "U4") (pin "38") (pinfunction "P4_13_38") (pintype "bidirectional"))
    )
    (net (code "98") (name "P4_14") (class "Default")
      (node (ref "U4") (pin "37") (pinfunction "P4_14_37") (pintype "bidirectional"))
    )
    (net (code "99") (name "P4_15") (class "Default")
      (node (ref "U4") (pin "36") (pinfunction "P4_15_36") (pintype "bidirectional"))
    )
    (net (code "100") (name "P5_00") (class "Default")
      (node (ref "J1") (pin "P$17") (pinfunction "P$17_P$17") (pintype "bidirectional"))
      (node (ref "U4") (pin "140") (pinfunction "P5_0/AN016_140") (pintype "bidirectional"))
    )
    (net (code "101") (name "P5_01") (class "Default")
      (node (ref "J1") (pin "P$18") (pinfunction "P$18_P$18") (pintype "bidirectional"))
      (node (ref "U4") (pin "141") (pinfunction "P5_1/AN116_141") (pintype "bidirectional"))
    )
    (net (code "102") (name "P5_02") (class "Default")
      (node (ref "J1") (pin "P$15") (pinfunction "P$15_P$15") (pintype "bidirectional"))
      (node (ref "U4") (pin "142") (pinfunction "P5_2/AN017_142") (pintype "bidirectional"))
    )
    (net (code "103") (name "P5_03") (class "Default")
      (node (ref "J1") (pin "P$16") (pinfunction "P$16_P$16") (pintype "bidirectional"))
      (node (ref "U4") (pin "143") (pinfunction "P5_3/AN117_143") (pintype "bidirectional"))
    )
    (net (code "104") (name "P5_04") (class "Default")
      (node (ref "J1") (pin "P$13") (pinfunction "P$13_P$13") (pintype "bidirectional"))
      (node (ref "U4") (pin "144") (pinfunction "P5_4/AN018_144") (pintype "bidirectional"))
    )
    (net (code "105") (name "P5_05") (class "Default")
      (node (ref "J1") (pin "P$14") (pinfunction "P$14_P$14") (pintype "bidirectional"))
      (node (ref "U4") (pin "145") (pinfunction "P5_5/AN118_145") (pintype "bidirectional"))
    )
    (net (code "106") (name "P5_06") (class "Default")
      (node (ref "J1") (pin "P$11") (pinfunction "P$11_P$11") (pintype "bidirectional"))
      (node (ref "U4") (pin "146") (pinfunction "P5_6/AN019_146") (pintype "bidirectional"))
    )
    (net (code "107") (name "P5_07") (class "Default")
      (node (ref "J1") (pin "P$12") (pinfunction "P$12_P$12") (pintype "bidirectional"))
      (node (ref "U4") (pin "147") (pinfunction "P5_7/AN119_147") (pintype "bidirectional"))
    )
    (net (code "108") (name "P5_11") (class "Default")
      (node (ref "J1") (pin "P$2") (pinfunction "P$2_P$2") (pintype "bidirectional"))
      (node (ref "U4") (pin "176") (pinfunction "P5_11_176") (pintype "bidirectional"))
    )
    (net (code "109") (name "P5_12") (class "Default")
      (node (ref "J1") (pin "P$1") (pinfunction "P$1_P$1") (pintype "bidirectional"))
      (node (ref "U4") (pin "175") (pinfunction "P5_12_175") (pintype "bidirectional"))
    )
    (net (code "110") (name "P5_13") (class "Default")
      (node (ref "J1") (pin "P$4") (pinfunction "P$4_P$4") (pintype "bidirectional"))
      (node (ref "U4") (pin "174") (pinfunction "P5_13_174") (pintype "bidirectional"))
    )
    (net (code "111") (name "P6_02") (class "Default")
      (node (ref "U4") (pin "120") (pinfunction "P6_2_120") (pintype "bidirectional"))
    )
    (net (code "112") (name "P6_03") (class "Default")
      (node (ref "U4") (pin "119") (pinfunction "P6_3_119") (pintype "bidirectional"))
    )
    (net (code "113") (name "P6_04") (class "Default")
      (node (ref "U4") (pin "118") (pinfunction "P6_4_118") (pintype "bidirectional"))
    )
    (net (code "114") (name "P6_05") (class "Default")
      (node (ref "U4") (pin "117") (pinfunction "P6_5_117") (pintype "bidirectional"))
    )
    (net (code "115") (name "P6_06") (class "Default")
      (node (ref "U4") (pin "116") (pinfunction "P6_6_116") (pintype "bidirectional"))
    )
    (net (code "116") (name "P6_07") (class "Default")
      (node (ref "U4") (pin "115") (pinfunction "P6_7_115") (pintype "bidirectional"))
    )
    (net (code "117") (name "P6_08") (class "Default")
      (node (ref "U4") (pin "99") (pinfunction "P6_8_99") (pintype "bidirectional"))
    )
    (net (code "118") (name "P6_09") (class "Default")
      (node (ref "U4") (pin "100") (pinfunction "P6_9_100") (pintype "bidirectional"))
    )
    (net (code "119") (name "P6_10") (class "Default")
      (node (ref "U4") (pin "101") (pinfunction "P6_10_101") (pintype "bidirectional"))
    )
    (net (code "120") (name "P6_11") (class "Default")
      (node (ref "U4") (pin "102") (pinfunction "P6_11_102") (pintype "bidirectional"))
    )
    (net (code "121") (name "P6_12") (class "Default")
      (node (ref "U4") (pin "103") (pinfunction "P6_12_103") (pintype "bidirectional"))
    )
    (net (code "122") (name "P6_13") (class "Default")
      (node (ref "U4") (pin "104") (pinfunction "P6_13_104") (pintype "bidirectional"))
    )
    (net (code "123") (name "P6_14") (class "Default")
      (node (ref "U4") (pin "105") (pinfunction "P6_14_105") (pintype "bidirectional"))
    )
    (net (code "124") (name "P6_15") (class "Default")
      (node (ref "U4") (pin "106") (pinfunction "P6_15_106") (pintype "bidirectional"))
    )
    (net (code "125") (name "P7_06") (class "Default")
      (node (ref "U4") (pin "14") (pinfunction "P7_6_14") (pintype "bidirectional"))
    )
    (net (code "126") (name "P7_07") (class "Default")
      (node (ref "U4") (pin "15") (pinfunction "P7_7_15") (pintype "bidirectional"))
    )
    (net (code "127") (name "P8_03") (class "Default")
      (node (ref "U4") (pin "136") (pinfunction "P8_3_136") (pintype "bidirectional"))
    )
    (net (code "128") (name "P8_04") (class "Default")
      (node (ref "U4") (pin "137") (pinfunction "P8_4_137") (pintype "bidirectional"))
    )
    (net (code "129") (name "P8_05") (class "Default")
      (node (ref "J1") (pin "P$3") (pinfunction "P$3_P$3") (pintype "bidirectional"))
      (node (ref "U4") (pin "173") (pinfunction "P8_5_173") (pintype "bidirectional"))
    )
    (net (code "130") (name "PA_00") (class "Default")
      (node (ref "U4") (pin "114") (pinfunction "PA_0_114") (pintype "bidirectional"))
    )
    (net (code "131") (name "PA_01") (class "Default")
      (node (ref "U4") (pin "113") (pinfunction "PA_1_113") (pintype "bidirectional"))
    )
    (net (code "132") (name "PA_08") (class "Default")
      (node (ref "U4") (pin "107") (pinfunction "PA_8_107") (pintype "bidirectional"))
    )
    (net (code "133") (name "PA_09") (class "Default")
      (node (ref "U4") (pin "108") (pinfunction "PA_9_108") (pintype "bidirectional"))
    )
    (net (code "134") (name "PA_10") (class "Default")
      (node (ref "U4") (pin "109") (pinfunction "PA_10_109") (pintype "bidirectional"))
    )
    (net (code "135") (name "PM0") (class "Default")
      (node (ref "U$2") (pin "P12") (pinfunction "PM0_P12") (pintype "bidirectional"))
      (node (ref "U4") (pin "126") (pinfunction "P1_6_126") (pintype "bidirectional"))
    )
    (net (code "136") (name "PM1") (class "Default")
      (node (ref "U$2") (pin "P13") (pinfunction "PM1_P13") (pintype "bidirectional"))
      (node (ref "U4") (pin "125") (pinfunction "P1_7_125") (pintype "bidirectional"))
    )
    (net (code "137") (name "R51") (class "Default")
      (node (ref "J4") (pin "12") (pinfunction "YHI_12") (pintype "bidirectional"))
      (node (ref "R23") (pin "P$1") (pinfunction "1_P$1") (pintype "passive"))
    )
    (net (code "138") (name "R52") (class "Default")
      (node (ref "J4") (pin "9") (pinfunction "GHI_9") (pintype "bidirectional"))
      (node (ref "R24") (pin "P$1") (pinfunction "1_P$1") (pintype "passive"))
    )
    (net (code "139") (name "RESET") (class "Default")
      (node (ref "C57") (pin "P$1") (pinfunction "1_P$1") (pintype "passive"))
      (node (ref "J11") (pin "9") (pinfunction "9_9") (pintype "passive"))
      (node (ref "R18") (pin "P$1") (pinfunction "1_P$1") (pintype "passive"))
      (node (ref "U4") (pin "67") (pinfunction "RES#_67") (pintype "bidirectional"))
    )
    (net (code "140") (name "REXT") (class "Default")
      (node (ref "C47") (pin "P$1") (pinfunction "1_P$1") (pintype "passive"))
      (node (ref "R25") (pin "P$2") (pinfunction "2_P$2") (pintype "passive"))
      (node (ref "U3") (pin "9") (pinfunction "REXT_9") (pintype "input"))
    )
    (net (code "141") (name "RST") (class "Default")
      (node (ref "U$2") (pin "P20") (pinfunction "RST_P20") (pintype "bidirectional"))
      (node (ref "U4") (pin "121") (pinfunction "P6_1_121") (pintype "bidirectional"))
    )
    (net (code "142") (name "RXD0") (class "Default")
      (node (ref "R31") (pin "P$2") (pinfunction "2_P$2") (pintype "passive"))
      (node (ref "U3") (pin "13") (pinfunction "RXD0_13") (pintype "bidirectional"))
    )
    (net (code "143") (name "RXD1") (class "Default")
      (node (ref "R30") (pin "P$2") (pinfunction "2_P$2") (pintype "passive"))
      (node (ref "U3") (pin "12") (pinfunction "RXD1_12") (pintype "bidirectional"))
    )
    (net (code "144") (name "RXER") (class "Default")
      (node (ref "R32") (pin "P$2") (pinfunction "2_P$2") (pintype "passive"))
      (node (ref "U3") (pin "17") (pinfunction "RXER_17") (pintype "bidirectional"))
    )
    (net (code "145") (name "RXM") (class "Default")
      (node (ref "J4") (pin "6") (pinfunction "RD-_6") (pintype "bidirectional"))
      (node (ref "U3") (pin "3") (pinfunction "RXM_3") (pintype "bidirectional"))
    )
    (net (code "146") (name "RXP") (class "Default")
      (node (ref "J4") (pin "3") (pinfunction "RD+_3") (pintype "bidirectional"))
      (node (ref "U3") (pin "4") (pinfunction "RXP_4") (pintype "bidirectional"))
    )
    (net (code "147") (name "SPI_0_CS_0") (class "Default")
      (node (ref "U$2") (pin "P16") (pinfunction "CS_P16") (pintype "bidirectional"))
      (node (ref "U4") (pin "129") (pinfunction "P1_3_129") (pintype "bidirectional"))
    )
    (net (code "148") (name "SPI_0_MISO") (class "Default")
      (node (ref "U$2") (pin "P18") (pinfunction "SDO_P18") (pintype "bidirectional"))
      (node (ref "U4") (pin "132") (pinfunction "P1_0_132") (pintype "bidirectional"))
    )
    (net (code "149") (name "SPI_0_MOSI") (class "Default")
      (node (ref "U$2") (pin "P15") (pinfunction "SDI_P15") (pintype "bidirectional"))
      (node (ref "U4") (pin "131") (pinfunction "P1_1_131") (pintype "bidirectional"))
    )
    (net (code "150") (name "SPI_0_SCLK") (class "Default")
      (node (ref "U$2") (pin "P17") (pinfunction "SCLK_P17") (pintype "bidirectional"))
      (node (ref "U4") (pin "130") (pinfunction "P1_2_130") (pintype "bidirectional"))
    )
    (net (code "151") (name "SPI_1_CS_0") (class "Default")
      (node (ref "J12") (pin "P$24") (pinfunction "CE0_P$24") (pintype "output"))
      (node (ref "U4") (pin "55") (pinfunction "P3_13_55") (pintype "bidirectional"))
    )
    (net (code "152") (name "SPI_1_CS_1") (class "Default")
      (node (ref "J12") (pin "P$26") (pinfunction "CE1_P$26") (pintype "output"))
      (node (ref "U4") (pin "74") (pinfunction "P3_12_74") (pintype "bidirectional"))
    )
    (net (code "153") (name "SPI_1_MISO") (class "Default")
      (node (ref "J12") (pin "P$21") (pinfunction "MISO_P$21") (pintype "input"))
      (node (ref "U4") (pin "54") (pinfunction "P2_2_54") (pintype "bidirectional"))
    )
    (net (code "154") (name "SPI_1_MOSI") (class "Default")
      (node (ref "J12") (pin "P$19") (pinfunction "MOSI_P$19") (pintype "output"))
      (node (ref "U4") (pin "53") (pinfunction "P2_3_53") (pintype "bidirectional"))
    )
    (net (code "155") (name "SPI_1_SCLK") (class "Default")
      (node (ref "J12") (pin "P$23") (pinfunction "SCLK_P$23") (pintype "output"))
      (node (ref "U4") (pin "52") (pinfunction "P2_4_52") (pintype "bidirectional"))
    )
    (net (code "156") (name "TCK") (class "Default")
      (node (ref "J11") (pin "7") (pinfunction "7_7") (pintype "passive"))
      (node (ref "U4") (pin "88") (pinfunction "P3_0_88") (pintype "bidirectional"))
    )
    (net (code "157") (name "TDI") (class "Default")
      (node (ref "J11") (pin "1") (pinfunction "1_1") (pintype "passive"))
      (node (ref "U4") (pin "91") (pinfunction "P1_10_91") (pintype "bidirectional"))
    )
    (net (code "158") (name "TDO") (class "Default")
      (node (ref "J11") (pin "3") (pinfunction "3_3") (pintype "passive"))
      (node (ref "U4") (pin "90") (pinfunction "P1_9_90") (pintype "bidirectional"))
    )
    (net (code "159") (name "TMS") (class "Default")
      (node (ref "J11") (pin "5") (pinfunction "5_5") (pintype "passive"))
      (node (ref "U4") (pin "89") (pinfunction "P1_8_89") (pintype "bidirectional"))
    )
    (net (code "160") (name "TXM") (class "Default")
      (node (ref "J4") (pin "2") (pinfunction "TD-_2") (pintype "bidirectional"))
      (node (ref "U3") (pin "5") (pinfunction "TXM_5") (pintype "bidirectional"))
    )
    (net (code "161") (name "TXP") (class "Default")
      (node (ref "J4") (pin "1") (pinfunction "TD+_1") (pintype "bidirectional"))
      (node (ref "U3") (pin "6") (pinfunction "TXP_6") (pintype "bidirectional"))
    )
    (net (code "162") (name "UC") (class "Default")
      (node (ref "C20") (pin "P$1") (pinfunction "P$1_P$1") (pintype "bidirectional"))
      (node (ref "U$2") (pin "P22") (pinfunction "VAC_240_P22") (pintype "bidirectional"))
      (node (ref "U$7") (pin "P$1") (pinfunction "P$1_P$1") (pintype "bidirectional"))
      (node (ref "U5") (pin "P$5") (pinfunction "AC_L_P$5") (pintype "bidirectional"))
    )
    (net (code "163") (name "USBHS_FAULT") (class "Default")
      (node (ref "R12") (pin "P$1") (pinfunction "1_P$1") (pintype "passive"))
      (node (ref "U2") (pin "3") (pinfunction "FLG_3") (pintype "input"))
      (node (ref "U4") (pin "78") (pinfunction "P3_8_78") (pintype "bidirectional"))
    )
    (net (code "164") (name "USBHS_N") (class "Default")
      (node (ref "J3") (pin "D-") (pinfunction "D-_D-") (pintype "bidirectional"))
      (node (ref "U4") (pin "31") (pinfunction "USBHS_DM_31") (pintype "bidirectional"))
    )
    (net (code "165") (name "USBHS_P") (class "Default")
      (node (ref "J3") (pin "D+") (pinfunction "D+_D+") (pintype "bidirectional"))
      (node (ref "U4") (pin "32") (pinfunction "USBHS_DP_32") (pintype "bidirectional"))
    )
    (net (code "166") (name "USBHS_VBUS") (class "Default")
      (node (ref "C11") (pin "P$1") (pinfunction "1_P$1") (pintype "passive"))
      (node (ref "C15") (pin "1") (pinfunction "1_1") (pintype "passive"))
      (node (ref "J3") (pin "VBUS") (pinfunction "VBUS_VBUS") (pintype "power_in"))
      (node (ref "U2") (pin "5") (pinfunction "OUT_5") (pintype "input"))
      (node (ref "U4") (pin "17") (pinfunction "PB_1_17") (pintype "bidirectional"))
    )
    (net (code "167") (name "USBHS_VBUSEN") (class "Default")
      (node (ref "R1") (pin "P$1") (pinfunction "1_P$1") (pintype "passive"))
      (node (ref "U2") (pin "1") (pinfunction "EN_1") (pintype "input"))
    )
    (net (code "168") (name "USB_N") (class "Default")
      (node (ref "R5") (pin "P$1") (pinfunction "1_P$1") (pintype "passive"))
      (node (ref "U4") (pin "46") (pinfunction "USB_DM_46") (pintype "bidirectional"))
    )
    (net (code "169") (name "USB_P") (class "Default")
      (node (ref "R6") (pin "P$1") (pinfunction "1_P$1") (pintype "passive"))
      (node (ref "U4") (pin "47") (pinfunction "USB_DP_47") (pintype "bidirectional"))
    )
    (net (code "170") (name "VCC") (class "Default")
      (node (ref "C21") (pin "P$1") (pinfunction "1_P$1") (pintype "passive"))
      (node (ref "C22") (pin "P$1") (pinfunction "1_P$1") (pintype "passive"))
      (node (ref "C23") (pin "1") (pinfunction "1_1") (pintype "passive"))
      (node (ref "C24") (pin "P$1") (pinfunction "1_P$1") (pintype "passive"))
      (node (ref "IC3") (pin "1") (pinfunction "IN_1") (pintype "input"))
      (node (ref "IC4") (pin "1") (pinfunction "IN_1") (pintype "input"))
      (node (ref "U$8") (pin "P+") (pinfunction "+_P+") (pintype "passive"))
      (node (ref "U5") (pin "P$2") (pinfunction "VOUT+_P$2") (pintype "bidirectional"))
    )
    (net (code "171") (name "VCL_F(FLASH)") (class "Default")
      (node (ref "C36") (pin "P$2") (pinfunction "2_P$2") (pintype "passive"))
      (node (ref "U4") (pin "112") (pinfunction "VCL_F(FLASH)_112") (pintype "bidirectional"))
    )
    (net (code "172") (name "VDD") (class "Default")
      (node (ref "C1") (pin "P$2") (pinfunction "2_P$2") (pintype "passive"))
      (node (ref "C10") (pin "P$2") (pinfunction "2_P$2") (pintype "passive"))
      (node (ref "C13") (pin "P$2") (pinfunction "2_P$2") (pintype "passive"))
      (node (ref "C14") (pin "P$2") (pinfunction "2_P$2") (pintype "passive"))
      (node (ref "C19") (pin "P$1") (pinfunction "1_P$1") (pintype "passive"))
      (node (ref "C2") (pin "P$2") (pinfunction "2_P$2") (pintype "passive"))
      (node (ref "C25") (pin "P$1") (pinfunction "1_P$1") (pintype "passive"))
      (node (ref "C26") (pin "1") (pinfunction "1_1") (pintype "passive"))
      (node (ref "C29") (pin "P$1") (pinfunction "1_P$1") (pintype "passive"))
      (node (ref "C30") (pin "P$2") (pinfunction "2_P$2") (pintype "passive"))
      (node (ref "C32") (pin "P$1") (pinfunction "1_P$1") (pintype "passive"))
      (node (ref "C48") (pin "1") (pinfunction "1_1") (pintype "passive"))
      (node (ref "C49") (pin "P$1") (pinfunction "1_P$1") (pintype "passive"))
      (node (ref "C54") (pin "P$2") (pinfunction "2_P$2") (pintype "passive"))
      (node (ref "C55") (pin "P$2") (pinfunction "2_P$2") (pintype "passive"))
      (node (ref "C56") (pin "P$2") (pinfunction "2_P$2") (pintype "passive"))
      (node (ref "C58") (pin "P$1") (pinfunction "1_P$1") (pintype "passive"))
      (node (ref "C59") (pin "P$1") (pinfunction "1_P$1") (pintype "passive"))
      (node (ref "C6") (pin "P$2") (pinfunction "2_P$2") (pintype "passive"))
      (node (ref "C60") (pin "P$1") (pinfunction "1_P$1") (pintype "passive"))
      (node (ref "C61") (pin "P$2") (pinfunction "2_P$2") (pintype "passive"))
      (node (ref "C62") (pin "P$1") (pinfunction "1_P$1") (pintype "passive"))
      (node (ref "C63") (pin "P$1") (pinfunction "1_P$1") (pintype "passive"))
      (node (ref "C9") (pin "P$1") (pinfunction "1_P$1") (pintype "passive"))
      (node (ref "FB2/2") (pin "1") (pinfunction "P$1_1") (pintype "bidirectional"))
      (node (ref "IC4") (pin "3") (pinfunction "OUT_3") (pintype "output"))
      (node (ref "J1") (pin "P$20") (pinfunction "P$20_P$20") (pintype "bidirectional"))
      (node (ref "J11") (pin "2") (pinfunction "2_2") (pintype "passive"))
      (node (ref "J11") (pin "4") (pinfunction "4_4") (pintype "passive"))
      (node (ref "J12") (pin "P$1") (pinfunction "3.3V_P$1") (pintype "power_in"))
      (node (ref "J12") (pin "P$17") (pinfunction "3.3V_P$17") (pintype "power_in"))
      (node (ref "R18") (pin "P$2") (pinfunction "2_P$2") (pintype "passive"))
      (node (ref "R23") (pin "P$2") (pinfunction "2_P$2") (pintype "passive"))
      (node (ref "R24") (pin "P$2") (pinfunction "2_P$2") (pintype "passive"))
      (node (ref "R26") (pin "P$2") (pinfunction "2_P$2") (pintype "passive"))
      (node (ref "R27") (pin "P$2") (pinfunction "2_P$2") (pintype "passive"))
      (node (ref "R28") (pin "P$2") (pinfunction "2_P$2") (pintype "passive"))
      (node (ref "R29") (pin "P$2") (pinfunction "2_P$2") (pintype "passive"))
      (node (ref "R8") (pin "P$1") (pinfunction "1_P$1") (pintype "passive"))
      (node (ref "U$2") (pin "P19") (pinfunction "VDD_P19") (pintype "bidirectional"))
      (node (ref "U1") (pin "16") (pinfunction "VBUS2_16") (pintype "bidirectional"))
      (node (ref "U3") (pin "14") (pinfunction "VDDIO_14") (pintype "power_in"))
      (node (ref "U4") (pin "110") (pinfunction "VCC(IO)5_110") (pintype "bidirectional"))
      (node (ref "U4") (pin "123") (pinfunction "VCC(IO)6_123") (pintype "bidirectional"))
      (node (ref "U4") (pin "138") (pinfunction "VCC(IO)7_138") (pintype "bidirectional"))
      (node (ref "U4") (pin "149") (pinfunction "VCC(IO)8_149") (pintype "bidirectional"))
      (node (ref "U4") (pin "154") (pinfunction "VREFH_154") (pintype "bidirectional"))
      (node (ref "U4") (pin "155") (pinfunction "AVCC0_155") (pintype "bidirectional"))
      (node (ref "U4") (pin "158") (pinfunction "VREFH0_158") (pintype "bidirectional"))
      (node (ref "U4") (pin "171") (pinfunction "VCC(IO)9_171") (pintype "bidirectional"))
      (node (ref "U4") (pin "25") (pinfunction "VCC1_25") (pintype "bidirectional"))
      (node (ref "U4") (pin "26") (pinfunction "AVCC_SUBHS_26") (pintype "bidirectional"))
      (node (ref "U4") (pin "34") (pinfunction "VCC_USBHS_34") (pintype "bidirectional"))
      (node (ref "U4") (pin "44") (pinfunction "P4_7_44") (pintype "bidirectional"))
      (node (ref "U4") (pin "48") (pinfunction "VCC_USB_48") (pintype "bidirectional"))
      (node (ref "U4") (pin "61") (pinfunction "VCC(IO)2_61") (pintype "bidirectional"))
      (node (ref "U4") (pin "84") (pinfunction "VCC(IO)3_84") (pintype "bidirectional"))
      (node (ref "U4") (pin "97") (pinfunction "VCC(IO)4_97") (pintype "bidirectional"))
      (node (ref "U6") (pin "7") (pinfunction "+VS_7") (pintype "power_in"))
      (node (ref "U7") (pin "7") (pinfunction "+VS_7") (pintype "power_in"))
    )
    (net (code "173") (name "VDD5") (class "Default")
      (node (ref "C27") (pin "P$1") (pinfunction "1_P$1") (pintype "passive"))
      (node (ref "C28") (pin "1") (pinfunction "1_1") (pintype "passive"))
      (node (ref "C5") (pin "P$1") (pinfunction "1_P$1") (pintype "passive"))
      (node (ref "C8") (pin "P$1") (pinfunction "1_P$1") (pintype "passive"))
      (node (ref "IC3") (pin "3") (pinfunction "OUT_3") (pintype "output"))
      (node (ref "J12") (pin "P$2") (pinfunction "5V_P$2") (pintype "power_in"))
      (node (ref "J12") (pin "P$4") (pinfunction "5V_P$4") (pintype "power_in"))
      (node (ref "R1") (pin "P$2") (pinfunction "2_P$2") (pintype "passive"))
      (node (ref "R12") (pin "P$2") (pinfunction "2_P$2") (pintype "passive"))
      (node (ref "R9") (pin "P$1") (pinfunction "1_P$1") (pintype "passive"))
      (node (ref "U2") (pin "4") (pinfunction "VIN_4") (pintype "input"))
    )
    (net (code "174") (name "VDD_1.2") (class "Default")
      (node (ref "C45") (pin "P$1") (pinfunction "1_P$1") (pintype "passive"))
      (node (ref "C46") (pin "P$1") (pinfunction "1_P$1") (pintype "passive"))
      (node (ref "U3") (pin "1") (pinfunction "VDD_1.2_1") (pintype "power_in"))
    )
    (net (code "175") (name "WARNOUT") (class "Default")
      (node (ref "U$2") (pin "P9") (pinfunction "WARNOUT_P9") (pintype "bidirectional"))
      (node (ref "U4") (pin "128") (pinfunction "P1_4_128") (pintype "bidirectional"))
    )
    (net (code "176") (name "XCIN") (class "Default")
      (node (ref "C50") (pin "P$1") (pinfunction "1_P$1") (pintype "passive"))
      (node (ref "U4") (pin "20") (pinfunction "XCIN_20") (pintype "bidirectional"))
      (node (ref "X3") (pin "P$1") (pinfunction "P$1_P$1") (pintype "bidirectional"))
    )
    (net (code "177") (name "XCOUT") (class "Default")
      (node (ref "C51") (pin "P$1") (pinfunction "1_P$1") (pintype "passive"))
      (node (ref "U4") (pin "21") (pinfunction "XCOUT_21") (pintype "bidirectional"))
      (node (ref "X3") (pin "P$2") (pinfunction "P$2_P$2") (pintype "bidirectional"))
    )
    (net (code "178") (name "XII") (class "Default")
      (node (ref "C42") (pin "P$1") (pinfunction "1_P$1") (pintype "passive"))
      (node (ref "U$3") (pin "1") (pinfunction "1_1") (pintype "bidirectional"))
      (node (ref "U3") (pin "8") (pinfunction "XI_8") (pintype "input"))
    )
    (net (code "179") (name "XOO") (class "Default")
      (node (ref "C41") (pin "P$1") (pinfunction "1_P$1") (pintype "passive"))
      (node (ref "U$3") (pin "3") (pinfunction "3_3") (pintype "bidirectional"))
      (node (ref "U3") (pin "7") (pinfunction "XO_7") (pintype "output"))
    )
    (net (code "180") (name "XTAL1") (class "Default")
      (node (ref "C52") (pin "P$1") (pinfunction "1_P$1") (pintype "passive"))
      (node (ref "U4") (pin "23") (pinfunction "P2_13/XTAL_23") (pintype "bidirectional"))
      (node (ref "X4") (pin "1") (pinfunction "1_1") (pintype "bidirectional"))
    )
    (net (code "181") (name "XTAL2") (class "Default")
      (node (ref "C53") (pin "P$1") (pinfunction "1_P$1") (pintype "passive"))
      (node (ref "U4") (pin "24") (pinfunction "P2_12/EXTAL_24") (pintype "bidirectional"))
      (node (ref "X4") (pin "3") (pinfunction "3_3") (pintype "bidirectional"))
    )
    (net (code "182") (name "ZX0") (class "Default")
      (node (ref "U$2") (pin "P2") (pinfunction "ZX0_P2") (pintype "bidirectional"))
      (node (ref "U4") (pin "135") (pinfunction "P8_2_135") (pintype "bidirectional"))
    )
    (net (code "183") (name "ZX1") (class "Default")
      (node (ref "U$2") (pin "P3") (pinfunction "ZX1_P3") (pintype "bidirectional"))
      (node (ref "U4") (pin "134") (pinfunction "P8_1_134") (pintype "bidirectional"))
    )
    (net (code "184") (name "ZX2") (class "Default")
      (node (ref "U$2") (pin "P4") (pinfunction "ZX2_P4") (pintype "bidirectional"))
      (node (ref "U4") (pin "133") (pinfunction "P8_0_133") (pintype "bidirectional"))
    )
    (net (code "185") (name "unconnected-(J2-ID-PadP$4)") (class "Default")
      (node (ref "J2") (pin "P$4") (pinfunction "ID_P$4") (pintype "bidirectional"))
    )
    (net (code "186") (name "unconnected-(U4-VBAT-Pad18)") (class "Default")
      (node (ref "U4") (pin "18") (pinfunction "VBAT_18") (pintype "bidirectional"))
    )
    (net (code "187") (name "unconnected-(U5-NC1-PadP$1)") (class "Default")
      (node (ref "U5") (pin "P$1") (pinfunction "NC1_P$1") (pintype "bidirectional"))
    )
    (net (code "188") (name "unconnected-(U5-NC2-PadP$4)") (class "Default")
      (node (ref "U5") (pin "P$4") (pinfunction "NC2_P$4") (pintype "bidirectional"))
    )
    (net (code "189") (name "unconnected-(U5-NC3-PadP$7)") (class "Default")
      (node (ref "U5") (pin "P$7") (pinfunction "NC3_P$7") (pintype "bidirectional"))
    )
    (net (code "190") (name "unconnected-(U6-NC-Pad4)") (class "Default")
      (node (ref "U6") (pin "4") (pinfunction "NC_4") (pintype "no_connect"))
    )
    (net (code "191") (name "unconnected-(U7-NC-Pad4)") (class "Default")
      (node (ref "U7") (pin "4") (pinfunction "NC_4") (pintype "no_connect"))
    )
  )
)
